# FPGA.net
KiCad netlist of a schematic drawn in Altium Designer
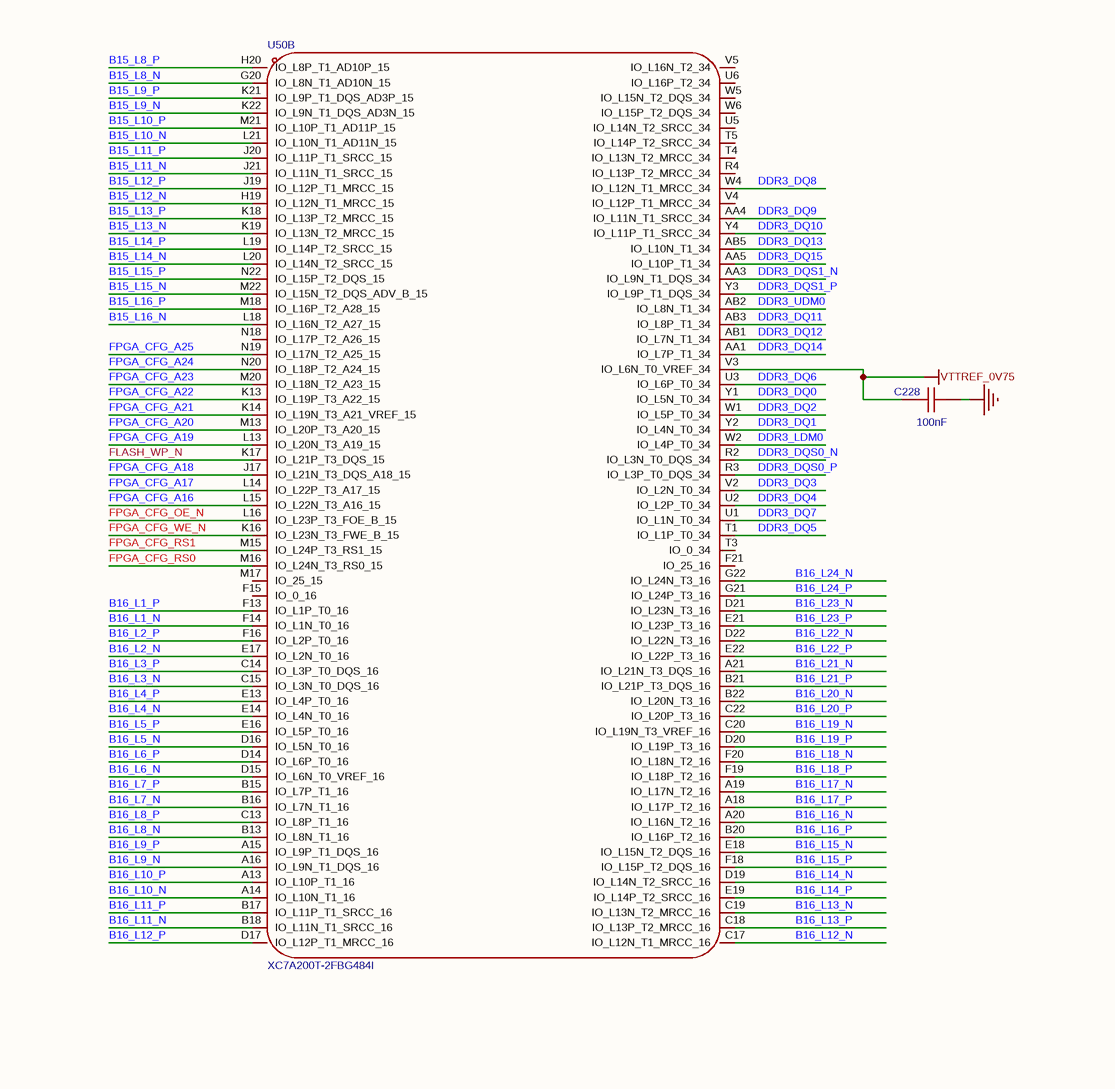
[diagram p0: FPGA.schdoc, top left]
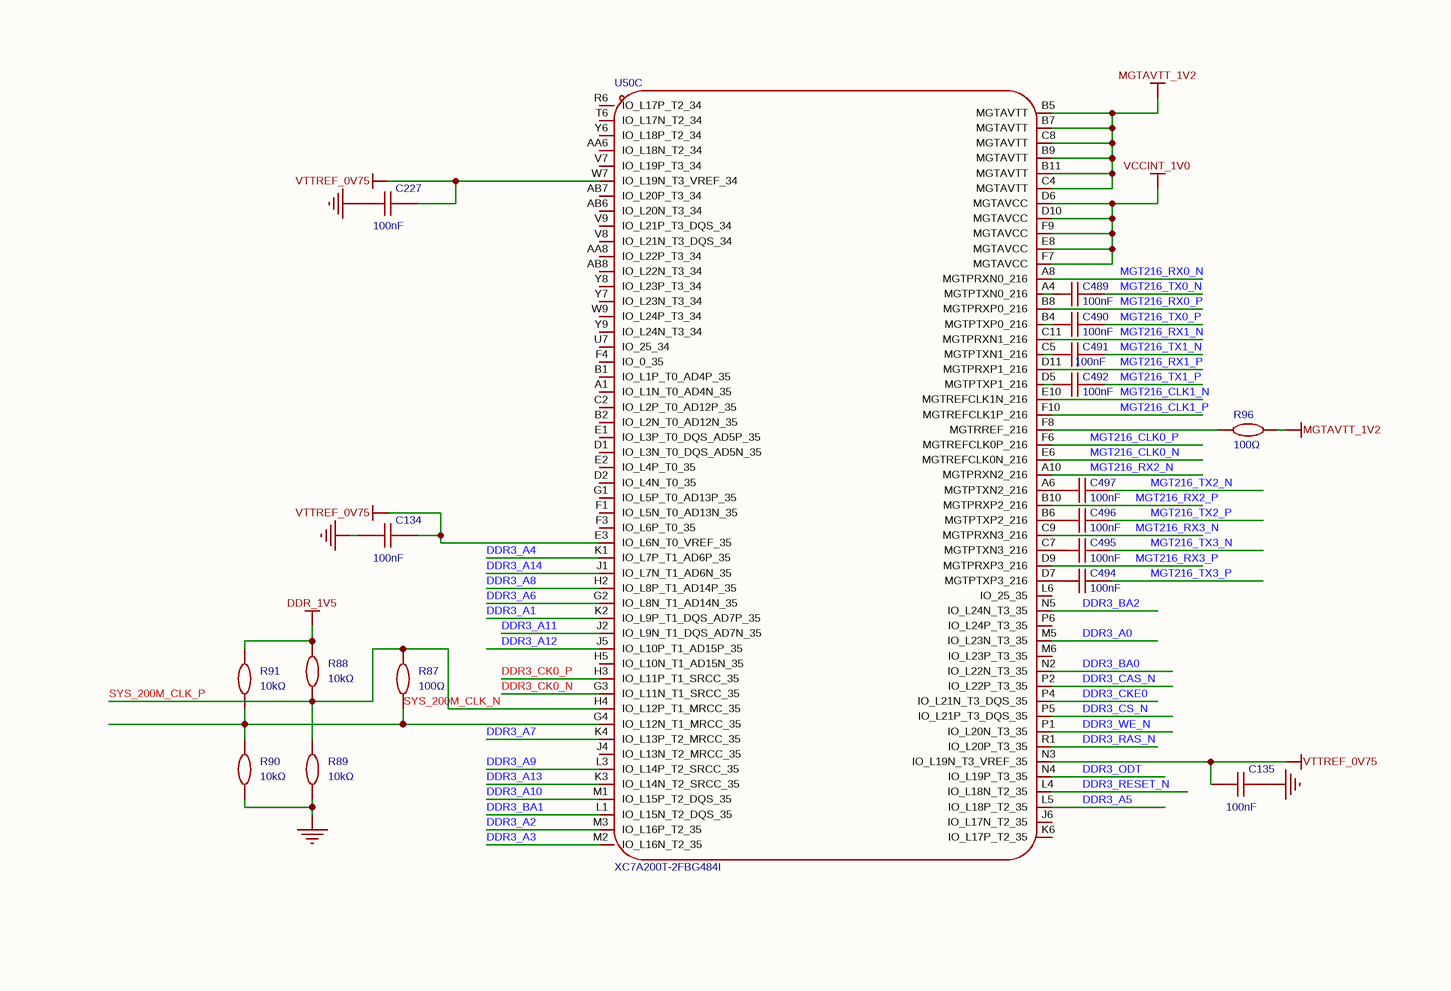
[diagram p1: FPGA.schdoc, top right]
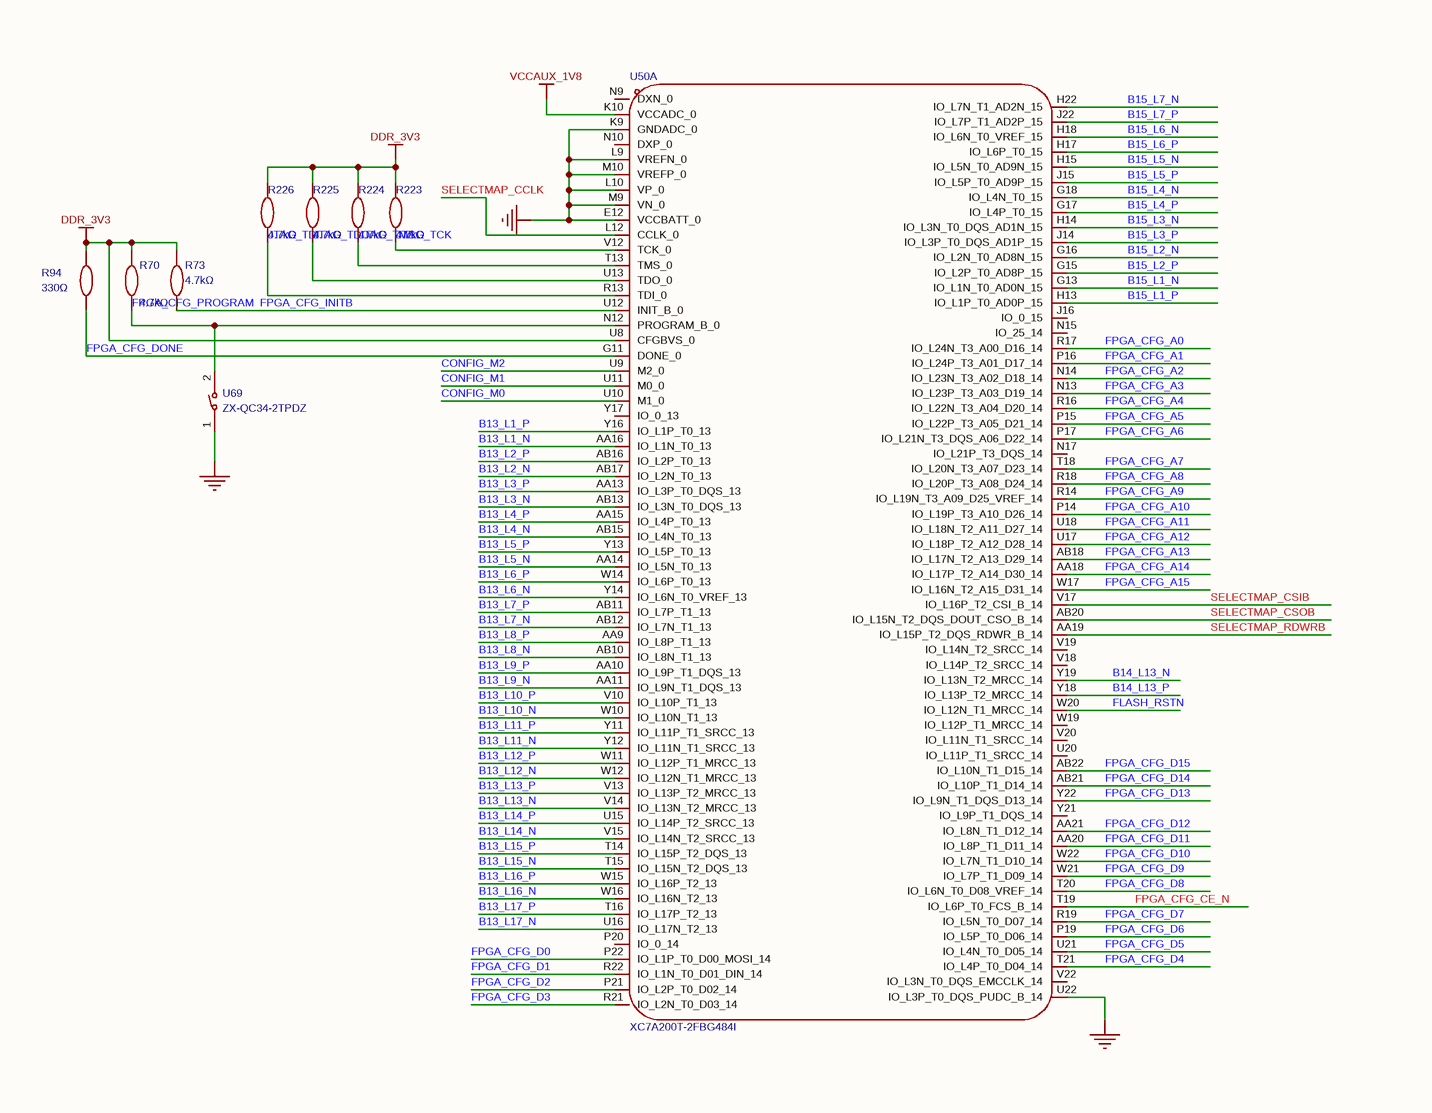
[diagram p2: FPGA.schdoc, bottom left]
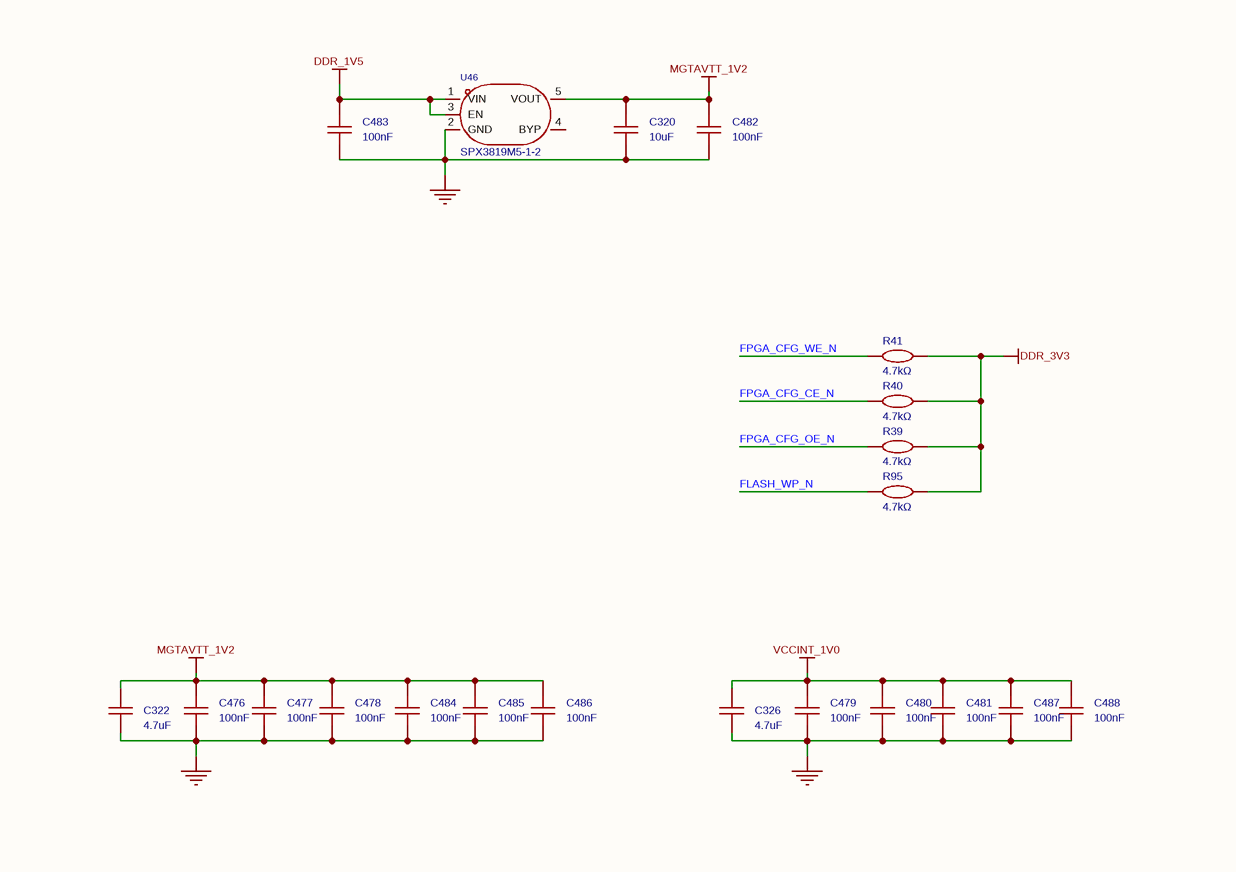
[diagram p3: FPGA.schdoc, bottom right]

(export (version "E")
  (design (tool "Eeschema 10.0.6"))
  (components
    (comp (ref "C134")
      (value "100nF")
      (footprint "C0402")
      (description "容值:100nF;精度:±10%;额定电压:50V;材质(温度系数):X7R;")
      (fields
        (field (name "MANUFACTURER") "muRata(村田)")
        (field (name "MANUFACTURER PART") "GRM155R71H104KE14D")
      )
      (libsource (lib "altium-import") (part "root_0_GRM155R71H104KE14D_"))
    )
    (comp (ref "C135")
      (value "100nF")
      (footprint "C0402")
      (description "容值:100nF;精度:±10%;额定电压:50V;材质(温度系数):X7R;")
      (fields
        (field (name "MANUFACTURER") "muRata(村田)")
        (field (name "MANUFACTURER PART") "GRM155R71H104KE14D")
      )
      (libsource (lib "altium-import") (part "root_0_GRM155R71H104KE14D_"))
    )
    (comp (ref "C227")
      (value "100nF")
      (footprint "C0402")
      (description "容值:100nF;精度:±10%;额定电压:50V;材质(温度系数):X7R;")
      (fields
        (field (name "MANUFACTURER") "muRata(村田)")
        (field (name "MANUFACTURER PART") "GRM155R71H104KE14D")
      )
      (libsource (lib "altium-import") (part "root_0_GRM155R71H104KE14D_"))
    )
    (comp (ref "C228")
      (value "100nF")
      (footprint "C0402")
      (description "容值:100nF;精度:±10%;额定电压:50V;材质(温度系数):X7R;")
      (fields
        (field (name "MANUFACTURER") "muRata(村田)")
        (field (name "MANUFACTURER PART") "GRM155R71H104KE14D")
      )
      (libsource (lib "altium-import") (part "root_0_mirrored_GRM155R71H104KE14D_"))
    )
    (comp (ref "C320")
      (value "10uF")
      (footprint "C0603")
      (description "容值:10uF;精度:±10%;额定电压:10V;材质(温度系数):X5R;")
      (fields
        (field (name "MANUFACTURER") "SAMSUNG(三星)")
        (field (name "MANUFACTURER PART") "CL10A106KP8NNNC")
      )
      (libsource (lib "altium-import") (part "root_1_CL10A106KP8NNNC_"))
    )
    (comp (ref "C322")
      (value "4.7uF")
      (footprint "C0603")
      (description "容值:4.7uF;精度:±10%;额定电压:16V;材质(温度系数):X5R;")
      (fields
        (field (name "MANUFACTURER PART") "CL10A475KO8NNNC")
        (field (name "MANUFACTURER") "SAMSUNG(三星)")
      )
      (libsource (lib "altium-import") (part "root_1_CL10A475KO8NNNC_"))
    )
    (comp (ref "C326")
      (value "4.7uF")
      (footprint "C0603")
      (description "容值:4.7uF;精度:±10%;额定电压:16V;材质(温度系数):X5R;")
      (fields
        (field (name "MANUFACTURER PART") "CL10A475KO8NNNC")
        (field (name "MANUFACTURER") "SAMSUNG(三星)")
      )
      (libsource (lib "altium-import") (part "root_1_CL10A475KO8NNNC_"))
    )
    (comp (ref "C476")
      (value "100nF")
      (footprint "C0402")
      (description "容值:100nF;精度:±10%;额定电压:50V;材质(温度系数):X7R;")
      (fields
        (field (name "MANUFACTURER") "muRata(村田)")
        (field (name "MANUFACTURER PART") "GRM155R71H104KE14D")
      )
      (libsource (lib "altium-import") (part "root_1_GRM155R71H104KE14D_"))
    )
    (comp (ref "C477")
      (value "100nF")
      (footprint "C0402")
      (description "容值:100nF;精度:±10%;额定电压:50V;材质(温度系数):X7R;")
      (fields
        (field (name "MANUFACTURER") "muRata(村田)")
        (field (name "MANUFACTURER PART") "GRM155R71H104KE14D")
      )
      (libsource (lib "altium-import") (part "root_1_GRM155R71H104KE14D_"))
    )
    (comp (ref "C478")
      (value "100nF")
      (footprint "C0402")
      (description "容值:100nF;精度:±10%;额定电压:50V;材质(温度系数):X7R;")
      (fields
        (field (name "MANUFACTURER") "muRata(村田)")
        (field (name "MANUFACTURER PART") "GRM155R71H104KE14D")
      )
      (libsource (lib "altium-import") (part "root_1_GRM155R71H104KE14D_"))
    )
    (comp (ref "C479")
      (value "100nF")
      (footprint "C0402")
      (description "容值:100nF;精度:±10%;额定电压:50V;材质(温度系数):X7R;")
      (fields
        (field (name "MANUFACTURER") "muRata(村田)")
        (field (name "MANUFACTURER PART") "GRM155R71H104KE14D")
      )
      (libsource (lib "altium-import") (part "root_1_GRM155R71H104KE14D_"))
    )
    (comp (ref "C480")
      (value "100nF")
      (footprint "C0402")
      (description "容值:100nF;精度:±10%;额定电压:50V;材质(温度系数):X7R;")
      (fields
        (field (name "MANUFACTURER") "muRata(村田)")
        (field (name "MANUFACTURER PART") "GRM155R71H104KE14D")
      )
      (libsource (lib "altium-import") (part "root_1_GRM155R71H104KE14D_"))
    )
    (comp (ref "C481")
      (value "100nF")
      (footprint "C0402")
      (description "容值:100nF;精度:±10%;额定电压:50V;材质(温度系数):X7R;")
      (fields
        (field (name "MANUFACTURER") "muRata(村田)")
        (field (name "MANUFACTURER PART") "GRM155R71H104KE14D")
      )
      (libsource (lib "altium-import") (part "root_1_GRM155R71H104KE14D_"))
    )
    (comp (ref "C482")
      (value "100nF")
      (footprint "C0402")
      (description "容值:100nF;精度:±10%;额定电压:50V;材质(温度系数):X7R;")
      (fields
        (field (name "MANUFACTURER") "muRata(村田)")
        (field (name "MANUFACTURER PART") "GRM155R71H104KE14D")
      )
      (libsource (lib "altium-import") (part "root_1_GRM155R71H104KE14D_"))
    )
    (comp (ref "C483")
      (value "100nF")
      (footprint "C0402")
      (description "容值:100nF;精度:±10%;额定电压:50V;材质(温度系数):X7R;")
      (fields
        (field (name "MANUFACTURER") "muRata(村田)")
        (field (name "MANUFACTURER PART") "GRM155R71H104KE14D")
      )
      (libsource (lib "altium-import") (part "root_1_GRM155R71H104KE14D_"))
    )
    (comp (ref "C484")
      (value "100nF")
      (footprint "C0402")
      (description "容值:100nF;精度:±10%;额定电压:50V;材质(温度系数):X7R;")
      (fields
        (field (name "MANUFACTURER") "muRata(村田)")
        (field (name "MANUFACTURER PART") "GRM155R71H104KE14D")
      )
      (libsource (lib "altium-import") (part "root_1_GRM155R71H104KE14D_"))
    )
    (comp (ref "C485")
      (value "100nF")
      (footprint "C0402")
      (description "容值:100nF;精度:±10%;额定电压:50V;材质(温度系数):X7R;")
      (fields
        (field (name "MANUFACTURER") "muRata(村田)")
        (field (name "MANUFACTURER PART") "GRM155R71H104KE14D")
      )
      (libsource (lib "altium-import") (part "root_1_GRM155R71H104KE14D_"))
    )
    (comp (ref "C486")
      (value "100nF")
      (footprint "C0402")
      (description "容值:100nF;精度:±10%;额定电压:50V;材质(温度系数):X7R;")
      (fields
        (field (name "MANUFACTURER") "muRata(村田)")
        (field (name "MANUFACTURER PART") "GRM155R71H104KE14D")
      )
      (libsource (lib "altium-import") (part "root_1_GRM155R71H104KE14D_"))
    )
    (comp (ref "C487")
      (value "100nF")
      (footprint "C0402")
      (description "容值:100nF;精度:±10%;额定电压:50V;材质(温度系数):X7R;")
      (fields
        (field (name "MANUFACTURER") "muRata(村田)")
        (field (name "MANUFACTURER PART") "GRM155R71H104KE14D")
      )
      (libsource (lib "altium-import") (part "root_1_GRM155R71H104KE14D_"))
    )
    (comp (ref "C488")
      (value "100nF")
      (footprint "C0402")
      (description "容值:100nF;精度:±10%;额定电压:50V;材质(温度系数):X7R;")
      (fields
        (field (name "MANUFACTURER") "muRata(村田)")
        (field (name "MANUFACTURER PART") "GRM155R71H104KE14D")
      )
      (libsource (lib "altium-import") (part "root_1_GRM155R71H104KE14D_"))
    )
    (comp (ref "C489")
      (value "100nF")
      (footprint "C0402")
      (description "容值:100nF;精度:±10%;额定电压:50V;材质(温度系数):X7R;")
      (fields
        (field (name "MANUFACTURER") "muRata(村田)")
        (field (name "MANUFACTURER PART") "GRM155R71H104KE14D")
      )
      (libsource (lib "altium-import") (part "root_2_GRM155R71H104KE14D_"))
    )
    (comp (ref "C490")
      (value "100nF")
      (footprint "C0402")
      (description "容值:100nF;精度:±10%;额定电压:50V;材质(温度系数):X7R;")
      (fields
        (field (name "MANUFACTURER") "muRata(村田)")
        (field (name "MANUFACTURER PART") "GRM155R71H104KE14D")
      )
      (libsource (lib "altium-import") (part "root_2_GRM155R71H104KE14D_"))
    )
    (comp (ref "C491")
      (value "100nF")
      (footprint "C0402")
      (description "容值:100nF;精度:±10%;额定电压:50V;材质(温度系数):X7R;")
      (fields
        (field (name "MANUFACTURER") "muRata(村田)")
        (field (name "MANUFACTURER PART") "GRM155R71H104KE14D")
      )
      (libsource (lib "altium-import") (part "root_2_GRM155R71H104KE14D_"))
    )
    (comp (ref "C492")
      (value "100nF")
      (footprint "C0402")
      (description "容值:100nF;精度:±10%;额定电压:50V;材质(温度系数):X7R;")
      (fields
        (field (name "MANUFACTURER") "muRata(村田)")
        (field (name "MANUFACTURER PART") "GRM155R71H104KE14D")
      )
      (libsource (lib "altium-import") (part "root_2_GRM155R71H104KE14D_"))
    )
    (comp (ref "C494")
      (value "100nF")
      (footprint "C0402")
      (description "容值:100nF;精度:±10%;额定电压:50V;材质(温度系数):X7R;")
      (fields
        (field (name "MANUFACTURER") "muRata(村田)")
        (field (name "MANUFACTURER PART") "GRM155R71H104KE14D")
      )
      (libsource (lib "altium-import") (part "root_2_GRM155R71H104KE14D_"))
    )
    (comp (ref "C495")
      (value "100nF")
      (footprint "C0402")
      (description "容值:100nF;精度:±10%;额定电压:50V;材质(温度系数):X7R;")
      (fields
        (field (name "MANUFACTURER") "muRata(村田)")
        (field (name "MANUFACTURER PART") "GRM155R71H104KE14D")
      )
      (libsource (lib "altium-import") (part "root_2_GRM155R71H104KE14D_"))
    )
    (comp (ref "C496")
      (value "100nF")
      (footprint "C0402")
      (description "容值:100nF;精度:±10%;额定电压:50V;材质(温度系数):X7R;")
      (fields
        (field (name "MANUFACTURER") "muRata(村田)")
        (field (name "MANUFACTURER PART") "GRM155R71H104KE14D")
      )
      (libsource (lib "altium-import") (part "root_2_GRM155R71H104KE14D_"))
    )
    (comp (ref "C497")
      (value "100nF")
      (footprint "C0402")
      (description "容值:100nF;精度:±10%;额定电压:50V;材质(温度系数):X7R;")
      (fields
        (field (name "MANUFACTURER") "muRata(村田)")
        (field (name "MANUFACTURER PART") "GRM155R71H104KE14D")
      )
      (libsource (lib "altium-import") (part "root_2_GRM155R71H104KE14D_"))
    )
    (comp (ref "R39")
      (value "4.7kΩ")
      (footprint "R0603")
      (description "电阻类型:厚膜电阻;阻值:4.7kΩ;精度:±1%;功率:100mW;最大工作电压:75V;温度系数:±100ppm/℃;")
      (fields
        (field (name "MANUFACTURER") "UNI-ROYAL(厚声)")
        (field (name "MANUFACTURER PART") "0603WAF4701T5E")
      )
      (libsource (lib "altium-import") (part "root_0_0603WAF4701T5E_"))
    )
    (comp (ref "R40")
      (value "4.7kΩ")
      (footprint "R0603")
      (description "电阻类型:厚膜电阻;阻值:4.7kΩ;精度:±1%;功率:100mW;最大工作电压:75V;温度系数:±100ppm/℃;")
      (fields
        (field (name "MANUFACTURER") "UNI-ROYAL(厚声)")
        (field (name "MANUFACTURER PART") "0603WAF4701T5E")
      )
      (libsource (lib "altium-import") (part "root_0_0603WAF4701T5E_"))
    )
    (comp (ref "R41")
      (value "4.7kΩ")
      (footprint "R0603")
      (description "电阻类型:厚膜电阻;阻值:4.7kΩ;精度:±1%;功率:100mW;最大工作电压:75V;温度系数:±100ppm/℃;")
      (fields
        (field (name "MANUFACTURER") "UNI-ROYAL(厚声)")
        (field (name "MANUFACTURER PART") "0603WAF4701T5E")
      )
      (libsource (lib "altium-import") (part "root_0_0603WAF4701T5E_"))
    )
    (comp (ref "R70")
      (value "4.7kΩ")
      (footprint "R0603")
      (description "电阻类型:厚膜电阻;阻值:4.7kΩ;精度:±1%;功率:100mW;最大工作电压:75V;温度系数:±100ppm/℃;")
      (fields
        (field (name "MANUFACTURER") "UNI-ROYAL(厚声)")
        (field (name "MANUFACTURER PART") "0603WAF4701T5E")
      )
      (libsource (lib "altium-import") (part "root_1_0603WAF4701T5E_"))
    )
    (comp (ref "R73")
      (value "4.7kΩ")
      (footprint "R0603")
      (description "电阻类型:厚膜电阻;阻值:4.7kΩ;精度:±1%;功率:100mW;最大工作电压:75V;温度系数:±100ppm/℃;")
      (fields
        (field (name "MANUFACTURER") "UNI-ROYAL(厚声)")
        (field (name "MANUFACTURER PART") "0603WAF4701T5E")
      )
      (libsource (lib "altium-import") (part "root_1_0603WAF4701T5E_"))
    )
    (comp (ref "R87")
      (value "100Ω")
      (footprint "R0603")
      (description "电阻类型:厚膜电阻;阻值:100Ω;精度:±1%;功率:100mW;最大工作电压:75V;温度系数:±200ppm/℃;")
      (fields
        (field (name "MANUFACTURER") "UNI-ROYAL(厚声)")
        (field (name "MANUFACTURERPART") "0603WAF1000T5E")
      )
      (libsource (lib "altium-import") (part "root_1_0603WAF1000T5E_"))
    )
    (comp (ref "R88")
      (value "10kΩ")
      (footprint "R0603")
      (description "电阻类型:厚膜电阻;阻值:10kΩ;精度:±1%;功率:100mW;最大工作电压:75V;温度系数:±100ppm/℃;")
      (fields
        (field (name "MANUFACTURER") "UNI-ROYAL(厚声)")
        (field (name "MANUFACTURER PART") "0603WAF1002T5E")
      )
      (libsource (lib "altium-import") (part "root_1_0603WAF1002T5E_"))
    )
    (comp (ref "R89")
      (value "10kΩ")
      (footprint "R0603")
      (description "电阻类型:厚膜电阻;阻值:10kΩ;精度:±1%;功率:100mW;最大工作电压:75V;温度系数:±100ppm/℃;")
      (fields
        (field (name "MANUFACTURER") "UNI-ROYAL(厚声)")
        (field (name "MANUFACTURER PART") "0603WAF1002T5E")
      )
      (libsource (lib "altium-import") (part "root_1_0603WAF1002T5E_"))
    )
    (comp (ref "R90")
      (value "10kΩ")
      (footprint "R0603")
      (description "电阻类型:厚膜电阻;阻值:10kΩ;精度:±1%;功率:100mW;最大工作电压:75V;温度系数:±100ppm/℃;")
      (fields
        (field (name "MANUFACTURER") "UNI-ROYAL(厚声)")
        (field (name "MANUFACTURER PART") "0603WAF1002T5E")
      )
      (libsource (lib "altium-import") (part "root_1_0603WAF1002T5E_"))
    )
    (comp (ref "R91")
      (value "10kΩ")
      (footprint "R0603")
      (description "电阻类型:厚膜电阻;阻值:10kΩ;精度:±1%;功率:100mW;最大工作电压:75V;温度系数:±100ppm/℃;")
      (fields
        (field (name "MANUFACTURER") "UNI-ROYAL(厚声)")
        (field (name "MANUFACTURER PART") "0603WAF1002T5E")
      )
      (libsource (lib "altium-import") (part "root_1_0603WAF1002T5E_"))
    )
    (comp (ref "R94")
      (value "330Ω")
      (footprint "R0603")
      (description "电阻类型:厚膜电阻;阻值:330Ω;精度:±1%;功率:100mW;最大工作电压:75V;温度系数:±100ppm/℃;")
      (fields
        (field (name "MANUFACTURER") "UNI-ROYAL(厚声)")
        (field (name "MANUFACTURER PART") "0603WAF3300T5E")
      )
      (libsource (lib "altium-import") (part "root_1_0603WAF3300T5E_"))
    )
    (comp (ref "R95")
      (value "4.7kΩ")
      (footprint "R0603")
      (description "电阻类型:厚膜电阻;阻值:4.7kΩ;精度:±1%;功率:100mW;最大工作电压:75V;温度系数:±100ppm/℃;")
      (fields
        (field (name "MANUFACTURER") "UNI-ROYAL(厚声)")
        (field (name "MANUFACTURER PART") "0603WAF4701T5E")
      )
      (libsource (lib "altium-import") (part "root_0_0603WAF4701T5E_"))
    )
    (comp (ref "R96")
      (value "100Ω")
      (footprint "R0402")
      (description "电阻类型:厚膜电阻;阻值:100Ω;精度:±1%;功率:62.5mW;最大工作电压:50V;温度系数:±200ppm/℃;")
      (fields
        (field (name "MANUFACTURER") "UNI-ROYAL(厚声)")
        (field (name "MANUFACTURERPART") "0402WGF1000TCE")
      )
      (libsource (lib "altium-import") (part "root_0_0402WGF1000TCE_"))
    )
    (comp (ref "R223")
      (value "4.7kΩ")
      (footprint "R0402")
      (description "电阻类型:厚膜电阻;阻值:4.7kΩ;精度:±1%;功率:62.5mW;最大工作电压:50V;温度系数:±100ppm/℃;")
      (fields
        (field (name "MANUFACTURER") "UNI-ROYAL(厚声)")
        (field (name "MANUFACTURER PART") "0402WGF4701TCE")
      )
      (libsource (lib "altium-import") (part "root_1_0402WGF4701TCE_"))
    )
    (comp (ref "R224")
      (value "4.7kΩ")
      (footprint "R0402")
      (description "电阻类型:厚膜电阻;阻值:4.7kΩ;精度:±1%;功率:62.5mW;最大工作电压:50V;温度系数:±100ppm/℃;")
      (fields
        (field (name "MANUFACTURER") "UNI-ROYAL(厚声)")
        (field (name "MANUFACTURER PART") "0402WGF4701TCE")
      )
      (libsource (lib "altium-import") (part "root_1_0402WGF4701TCE_"))
    )
    (comp (ref "R225")
      (value "4.7kΩ")
      (footprint "R0402")
      (description "电阻类型:厚膜电阻;阻值:4.7kΩ;精度:±1%;功率:62.5mW;最大工作电压:50V;温度系数:±100ppm/℃;")
      (fields
        (field (name "MANUFACTURER") "UNI-ROYAL(厚声)")
        (field (name "MANUFACTURER PART") "0402WGF4701TCE")
      )
      (libsource (lib "altium-import") (part "root_1_0402WGF4701TCE_"))
    )
    (comp (ref "R226")
      (value "4.7kΩ")
      (footprint "R0402")
      (description "电阻类型:厚膜电阻;阻值:4.7kΩ;精度:±1%;功率:62.5mW;最大工作电压:50V;温度系数:±100ppm/℃;")
      (fields
        (field (name "MANUFACTURER") "UNI-ROYAL(厚声)")
        (field (name "MANUFACTURER PART") "0402WGF4701TCE")
      )
      (libsource (lib "altium-import") (part "root_1_0402WGF4701TCE_"))
    )
    (comp (ref "U46")
      (value "SPX3819M5-1-2")
      (footprint "SOT-23-5_L2.9-W1.6-P0.95-LS2.8-BR")
      (fields (field (name "MANUFACTURER") "SIPEX"))
      (libsource (lib "altium-import") (part "root_0_SPX3819M5-1-2_"))
    )
    (comp (ref "U50")
      (value "XC7A200T-2FBG484I")
      (footprint "FBGA-484_L23.0-W23.0-R22-C22-P1.00-TL")
      (fields (field (name "MANUFACTURER") "AMD/XILINX(赛灵思)"))
      (libsource (lib "altium-import") (part "root_0_XC7A200T-2FBG484I_"))
    )
    (comp (ref "U69")
      (value "ZX-QC34-2TPDZ")
      (footprint "KEY-SMD_L3.9-W3.0-LS5.0-EH")
      (fields (field (name "MANUFACTURER") "Megastar(兆星)"))
      (libsource (lib "altium-import") (part "root_1_ZX-QC34-2TPDZ_"))
    )
  )
  (nets
    (net (code "1") (name "/B13_L1_N") (class "Default")
      (node (ref "U50") (pin "AA16") (pinfunction "IO_L1N_T0_13_AA16") (pintype "passive"))
    )
    (net (code "2") (name "/B13_L1_P") (class "Default")
      (node (ref "U50") (pin "Y16") (pinfunction "IO_L1P_T0_13_Y16") (pintype "passive"))
    )
    (net (code "3") (name "/B13_L2_N") (class "Default")
      (node (ref "U50") (pin "AB17") (pinfunction "IO_L2N_T0_13_AB17") (pintype "passive"))
    )
    (net (code "4") (name "/B13_L2_P") (class "Default")
      (node (ref "U50") (pin "AB16") (pinfunction "IO_L2P_T0_13_AB16") (pintype "passive"))
    )
    (net (code "5") (name "/B13_L3_N") (class "Default")
      (node (ref "U50") (pin "AB13") (pinfunction "IO_L3N_T0_DQS_13_AB13") (pintype "passive"))
    )
    (net (code "6") (name "/B13_L3_P") (class "Default")
      (node (ref "U50") (pin "AA13") (pinfunction "IO_L3P_T0_DQS_13_AA13") (pintype "passive"))
    )
    (net (code "7") (name "/B13_L4_N") (class "Default")
      (node (ref "U50") (pin "AB15") (pinfunction "IO_L4N_T0_13_AB15") (pintype "passive"))
    )
    (net (code "8") (name "/B13_L4_P") (class "Default")
      (node (ref "U50") (pin "AA15") (pinfunction "IO_L4P_T0_13_AA15") (pintype "passive"))
    )
    (net (code "9") (name "/B13_L5_N") (class "Default")
      (node (ref "U50") (pin "AA14") (pinfunction "IO_L5N_T0_13_AA14") (pintype "passive"))
    )
    (net (code "10") (name "/B13_L5_P") (class "Default")
      (node (ref "U50") (pin "Y13") (pinfunction "IO_L5P_T0_13_Y13") (pintype "passive"))
    )
    (net (code "11") (name "/B13_L6_N") (class "Default")
      (node (ref "U50") (pin "Y14") (pinfunction "IO_L6N_T0_VREF_13_Y14") (pintype "passive"))
    )
    (net (code "12") (name "/B13_L6_P") (class "Default")
      (node (ref "U50") (pin "W14") (pinfunction "IO_L6P_T0_13_W14") (pintype "passive"))
    )
    (net (code "13") (name "/B13_L7_N") (class "Default")
      (node (ref "U50") (pin "AB12") (pinfunction "IO_L7N_T1_13_AB12") (pintype "passive"))
    )
    (net (code "14") (name "/B13_L7_P") (class "Default")
      (node (ref "U50") (pin "AB11") (pinfunction "IO_L7P_T1_13_AB11") (pintype "passive"))
    )
    (net (code "15") (name "/B13_L8_N") (class "Default")
      (node (ref "U50") (pin "AB10") (pinfunction "IO_L8N_T1_13_AB10") (pintype "passive"))
    )
    (net (code "16") (name "/B13_L8_P") (class "Default")
      (node (ref "U50") (pin "AA9") (pinfunction "IO_L8P_T1_13_AA9") (pintype "passive"))
    )
    (net (code "17") (name "/B13_L9_N") (class "Default")
      (node (ref "U50") (pin "AA11") (pinfunction "IO_L9N_T1_DQS_13_AA11") (pintype "passive"))
    )
    (net (code "18") (name "/B13_L9_P") (class "Default")
      (node (ref "U50") (pin "AA10") (pinfunction "IO_L9P_T1_DQS_13_AA10") (pintype "passive"))
    )
    (net (code "19") (name "/B13_L10_N") (class "Default")
      (node (ref "U50") (pin "W10") (pinfunction "IO_L10N_T1_13_W10") (pintype "passive"))
    )
    (net (code "20") (name "/B13_L10_P") (class "Default")
      (node (ref "U50") (pin "V10") (pinfunction "IO_L10P_T1_13_V10") (pintype "passive"))
    )
    (net (code "21") (name "/B13_L11_N") (class "Default")
      (node (ref "U50") (pin "Y12") (pinfunction "IO_L11N_T1_SRCC_13_Y12") (pintype "passive"))
    )
    (net (code "22") (name "/B13_L11_P") (class "Default")
      (node (ref "U50") (pin "Y11") (pinfunction "IO_L11P_T1_SRCC_13_Y11") (pintype "passive"))
    )
    (net (code "23") (name "/B13_L12_N") (class "Default")
      (node (ref "U50") (pin "W12") (pinfunction "IO_L12N_T1_MRCC_13_W12") (pintype "passive"))
    )
    (net (code "24") (name "/B13_L12_P") (class "Default")
      (node (ref "U50") (pin "W11") (pinfunction "IO_L12P_T1_MRCC_13_W11") (pintype "passive"))
    )
    (net (code "25") (name "/B13_L13_N") (class "Default")
      (node (ref "U50") (pin "V14") (pinfunction "IO_L13N_T2_MRCC_13_V14") (pintype "passive"))
    )
    (net (code "26") (name "/B13_L13_P") (class "Default")
      (node (ref "U50") (pin "V13") (pinfunction "IO_L13P_T2_MRCC_13_V13") (pintype "passive"))
    )
    (net (code "27") (name "/B13_L14_N") (class "Default")
      (node (ref "U50") (pin "V15") (pinfunction "IO_L14N_T2_SRCC_13_V15") (pintype "passive"))
    )
    (net (code "28") (name "/B13_L14_P") (class "Default")
      (node (ref "U50") (pin "U15") (pinfunction "IO_L14P_T2_SRCC_13_U15") (pintype "passive"))
    )
    (net (code "29") (name "/B13_L15_N") (class "Default")
      (node (ref "U50") (pin "T15") (pinfunction "IO_L15N_T2_DQS_13_T15") (pintype "passive"))
    )
    (net (code "30") (name "/B13_L15_P") (class "Default")
      (node (ref "U50") (pin "T14") (pinfunction "IO_L15P_T2_DQS_13_T14") (pintype "passive"))
    )
    (net (code "31") (name "/B13_L16_N") (class "Default")
      (node (ref "U50") (pin "W16") (pinfunction "IO_L16N_T2_13_W16") (pintype "passive"))
    )
    (net (code "32") (name "/B13_L16_P") (class "Default")
      (node (ref "U50") (pin "W15") (pinfunction "IO_L16P_T2_13_W15") (pintype "passive"))
    )
    (net (code "33") (name "/B13_L17_N") (class "Default")
      (node (ref "U50") (pin "U16") (pinfunction "IO_L17N_T2_13_U16") (pintype "passive"))
    )
    (net (code "34") (name "/B13_L17_P") (class "Default")
      (node (ref "U50") (pin "T16") (pinfunction "IO_L17P_T2_13_T16") (pintype "passive"))
    )
    (net (code "35") (name "/B14_L13_N") (class "Default")
      (node (ref "U50") (pin "Y19") (pinfunction "IO_L13N_T2_MRCC_14_Y19") (pintype "passive"))
    )
    (net (code "36") (name "/B14_L13_P") (class "Default")
      (node (ref "U50") (pin "Y18") (pinfunction "IO_L13P_T2_MRCC_14_Y18") (pintype "passive"))
    )
    (net (code "37") (name "/B15_L1_N") (class "Default")
      (node (ref "U50") (pin "G13") (pinfunction "IO_L1N_T0_AD0N_15_G13") (pintype "passive"))
    )
    (net (code "38") (name "/B15_L1_P") (class "Default")
      (node (ref "U50") (pin "H13") (pinfunction "IO_L1P_T0_AD0P_15_H13") (pintype "passive"))
    )
    (net (code "39") (name "/B15_L2_N") (class "Default")
      (node (ref "U50") (pin "G16") (pinfunction "IO_L2N_T0_AD8N_15_G16") (pintype "passive"))
    )
    (net (code "40") (name "/B15_L2_P") (class "Default")
      (node (ref "U50") (pin "G15") (pinfunction "IO_L2P_T0_AD8P_15_G15") (pintype "passive"))
    )
    (net (code "41") (name "/B15_L3_N") (class "Default")
      (node (ref "U50") (pin "H14") (pinfunction "IO_L3N_T0_DQS_AD1N_15_H14") (pintype "passive"))
    )
    (net (code "42") (name "/B15_L3_P") (class "Default")
      (node (ref "U50") (pin "J14") (pinfunction "IO_L3P_T0_DQS_AD1P_15_J14") (pintype "passive"))
    )
    (net (code "43") (name "/B15_L4_N") (class "Default")
      (node (ref "U50") (pin "G18") (pinfunction "IO_L4N_T0_15_G18") (pintype "passive"))
    )
    (net (code "44") (name "/B15_L4_P") (class "Default")
      (node (ref "U50") (pin "G17") (pinfunction "IO_L4P_T0_15_G17") (pintype "passive"))
    )
    (net (code "45") (name "/B15_L5_N") (class "Default")
      (node (ref "U50") (pin "H15") (pinfunction "IO_L5N_T0_AD9N_15_H15") (pintype "passive"))
    )
    (net (code "46") (name "/B15_L5_P") (class "Default")
      (node (ref "U50") (pin "J15") (pinfunction "IO_L5P_T0_AD9P_15_J15") (pintype "passive"))
    )
    (net (code "47") (name "/B15_L6_N") (class "Default")
      (node (ref "U50") (pin "H18") (pinfunction "IO_L6N_T0_VREF_15_H18") (pintype "passive"))
    )
    (net (code "48") (name "/B15_L6_P") (class "Default")
      (node (ref "U50") (pin "H17") (pinfunction "IO_L6P_T0_15_H17") (pintype "passive"))
    )
    (net (code "49") (name "/B15_L7_N") (class "Default")
      (node (ref "U50") (pin "H22") (pinfunction "IO_L7N_T1_AD2N_15_H22") (pintype "passive"))
    )
    (net (code "50") (name "/B15_L7_P") (class "Default")
      (node (ref "U50") (pin "J22") (pinfunction "IO_L7P_T1_AD2P_15_J22") (pintype "passive"))
    )
    (net (code "51") (name "/B15_L8_N") (class "Default")
      (node (ref "U50") (pin "G20") (pinfunction "IO_L8N_T1_AD10N_15_G20") (pintype "passive"))
    )
    (net (code "52") (name "/B15_L8_P") (class "Default")
      (node (ref "U50") (pin "H20") (pinfunction "IO_L8P_T1_AD10P_15_H20") (pintype "passive"))
    )
    (net (code "53") (name "/B15_L9_N") (class "Default")
      (node (ref "U50") (pin "K22") (pinfunction "IO_L9N_T1_DQS_AD3N_15_K22") (pintype "passive"))
    )
    (net (code "54") (name "/B15_L9_P") (class "Default")
      (node (ref "U50") (pin "K21") (pinfunction "IO_L9P_T1_DQS_AD3P_15_K21") (pintype "passive"))
    )
    (net (code "55") (name "/B15_L10_N") (class "Default")
      (node (ref "U50") (pin "L21") (pinfunction "IO_L10N_T1_AD11N_15_L21") (pintype "passive"))
    )
    (net (code "56") (name "/B15_L10_P") (class "Default")
      (node (ref "U50") (pin "M21") (pinfunction "IO_L10P_T1_AD11P_15_M21") (pintype "passive"))
    )
    (net (code "57") (name "/B15_L11_N") (class "Default")
      (node (ref "U50") (pin "J21") (pinfunction "IO_L11N_T1_SRCC_15_J21") (pintype "passive"))
    )
    (net (code "58") (name "/B15_L11_P") (class "Default")
      (node (ref "U50") (pin "J20") (pinfunction "IO_L11P_T1_SRCC_15_J20") (pintype "passive"))
    )
    (net (code "59") (name "/B15_L12_N") (class "Default")
      (node (ref "U50") (pin "H19") (pinfunction "IO_L12N_T1_MRCC_15_H19") (pintype "passive"))
    )
    (net (code "60") (name "/B15_L12_P") (class "Default")
      (node (ref "U50") (pin "J19") (pinfunction "IO_L12P_T1_MRCC_15_J19") (pintype "passive"))
    )
    (net (code "61") (name "/B15_L13_N") (class "Default")
      (node (ref "U50") (pin "K19") (pinfunction "IO_L13N_T2_MRCC_15_K19") (pintype "passive"))
    )
    (net (code "62") (name "/B15_L13_P") (class "Default")
      (node (ref "U50") (pin "K18") (pinfunction "IO_L13P_T2_MRCC_15_K18") (pintype "passive"))
    )
    (net (code "63") (name "/B15_L14_N") (class "Default")
      (node (ref "U50") (pin "L20") (pinfunction "IO_L14N_T2_SRCC_15_L20") (pintype "passive"))
    )
    (net (code "64") (name "/B15_L14_P") (class "Default")
      (node (ref "U50") (pin "L19") (pinfunction "IO_L14P_T2_SRCC_15_L19") (pintype "passive"))
    )
    (net (code "65") (name "/B15_L15_N") (class "Default")
      (node (ref "U50") (pin "M22") (pinfunction "IO_L15N_T2_DQS_ADV_B_15_M22") (pintype "passive"))
    )
    (net (code "66") (name "/B15_L15_P") (class "Default")
      (node (ref "U50") (pin "N22") (pinfunction "IO_L15P_T2_DQS_15_N22") (pintype "passive"))
    )
    (net (code "67") (name "/B15_L16_N") (class "Default")
      (node (ref "U50") (pin "L18") (pinfunction "IO_L16N_T2_A27_15_L18") (pintype "passive"))
    )
    (net (code "68") (name "/B15_L16_P") (class "Default")
      (node (ref "U50") (pin "M18") (pinfunction "IO_L16P_T2_A28_15_M18") (pintype "passive"))
    )
    (net (code "69") (name "/B16_L1_N") (class "Default")
      (node (ref "U50") (pin "F14") (pinfunction "IO_L1N_T0_16_F14") (pintype "passive"))
    )
    (net (code "70") (name "/B16_L1_P") (class "Default")
      (node (ref "U50") (pin "F13") (pinfunction "IO_L1P_T0_16_F13") (pintype "passive"))
    )
    (net (code "71") (name "/B16_L2_N") (class "Default")
      (node (ref "U50") (pin "E17") (pinfunction "IO_L2N_T0_16_E17") (pintype "passive"))
    )
    (net (code "72") (name "/B16_L2_P") (class "Default")
      (node (ref "U50") (pin "F16") (pinfunction "IO_L2P_T0_16_F16") (pintype "passive"))
    )
    (net (code "73") (name "/B16_L3_N") (class "Default")
      (node (ref "U50") (pin "C15") (pinfunction "IO_L3N_T0_DQS_16_C15") (pintype "passive"))
    )
    (net (code "74") (name "/B16_L3_P") (class "Default")
      (node (ref "U50") (pin "C14") (pinfunction "IO_L3P_T0_DQS_16_C14") (pintype "passive"))
    )
    (net (code "75") (name "/B16_L4_N") (class "Default")
      (node (ref "U50") (pin "E14") (pinfunction "IO_L4N_T0_16_E14") (pintype "passive"))
    )
    (net (code "76") (name "/B16_L4_P") (class "Default")
      (node (ref "U50") (pin "E13") (pinfunction "IO_L4P_T0_16_E13") (pintype "passive"))
    )
    (net (code "77") (name "/B16_L5_N") (class "Default")
      (node (ref "U50") (pin "D16") (pinfunction "IO_L5N_T0_16_D16") (pintype "passive"))
    )
    (net (code "78") (name "/B16_L5_P") (class "Default")
      (node (ref "U50") (pin "E16") (pinfunction "IO_L5P_T0_16_E16") (pintype "passive"))
    )
    (net (code "79") (name "/B16_L6_N") (class "Default")
      (node (ref "U50") (pin "D15") (pinfunction "IO_L6N_T0_VREF_16_D15") (pintype "passive"))
    )
    (net (code "80") (name "/B16_L6_P") (class "Default")
      (node (ref "U50") (pin "D14") (pinfunction "IO_L6P_T0_16_D14") (pintype "passive"))
    )
    (net (code "81") (name "/B16_L7_N") (class "Default")
      (node (ref "U50") (pin "B16") (pinfunction "IO_L7N_T1_16_B16") (pintype "passive"))
    )
    (net (code "82") (name "/B16_L7_P") (class "Default")
      (node (ref "U50") (pin "B15") (pinfunction "IO_L7P_T1_16_B15") (pintype "passive"))
    )
    (net (code "83") (name "/B16_L8_N") (class "Default")
      (node (ref "U50") (pin "B13") (pinfunction "IO_L8N_T1_16_B13") (pintype "passive"))
    )
    (net (code "84") (name "/B16_L8_P") (class "Default")
      (node (ref "U50") (pin "C13") (pinfunction "IO_L8P_T1_16_C13") (pintype "passive"))
    )
    (net (code "85") (name "/B16_L9_N") (class "Default")
      (node (ref "U50") (pin "A16") (pinfunction "IO_L9N_T1_DQS_16_A16") (pintype "passive"))
    )
    (net (code "86") (name "/B16_L9_P") (class "Default")
      (node (ref "U50") (pin "A15") (pinfunction "IO_L9P_T1_DQS_16_A15") (pintype "passive"))
    )
    (net (code "87") (name "/B16_L10_N") (class "Default")
      (node (ref "U50") (pin "A14") (pinfunction "IO_L10N_T1_16_A14") (pintype "passive"))
    )
    (net (code "88") (name "/B16_L10_P") (class "Default")
      (node (ref "U50") (pin "A13") (pinfunction "IO_L10P_T1_16_A13") (pintype "passive"))
    )
    (net (code "89") (name "/B16_L11_N") (class "Default")
      (node (ref "U50") (pin "B18") (pinfunction "IO_L11N_T1_SRCC_16_B18") (pintype "passive"))
    )
    (net (code "90") (name "/B16_L11_P") (class "Default")
      (node (ref "U50") (pin "B17") (pinfunction "IO_L11P_T1_SRCC_16_B17") (pintype "passive"))
    )
    (net (code "91") (name "/B16_L12_N") (class "Default")
      (node (ref "U50") (pin "C17") (pinfunction "IO_L12N_T1_MRCC_16_C17") (pintype "passive"))
    )
    (net (code "92") (name "/B16_L12_P") (class "Default")
      (node (ref "U50") (pin "D17") (pinfunction "IO_L12P_T1_MRCC_16_D17") (pintype "passive"))
    )
    (net (code "93") (name "/B16_L13_N") (class "Default")
      (node (ref "U50") (pin "C19") (pinfunction "IO_L13N_T2_MRCC_16_C19") (pintype "passive"))
    )
    (net (code "94") (name "/B16_L13_P") (class "Default")
      (node (ref "U50") (pin "C18") (pinfunction "IO_L13P_T2_MRCC_16_C18") (pintype "passive"))
    )
    (net (code "95") (name "/B16_L14_N") (class "Default")
      (node (ref "U50") (pin "D19") (pinfunction "IO_L14N_T2_SRCC_16_D19") (pintype "passive"))
    )
    (net (code "96") (name "/B16_L14_P") (class "Default")
      (node (ref "U50") (pin "E19") (pinfunction "IO_L14P_T2_SRCC_16_E19") (pintype "passive"))
    )
    (net (code "97") (name "/B16_L15_N") (class "Default")
      (node (ref "U50") (pin "E18") (pinfunction "IO_L15N_T2_DQS_16_E18") (pintype "passive"))
    )
    (net (code "98") (name "/B16_L15_P") (class "Default")
      (node (ref "U50") (pin "F18") (pinfunction "IO_L15P_T2_DQS_16_F18") (pintype "passive"))
    )
    (net (code "99") (name "/B16_L16_N") (class "Default")
      (node (ref "U50") (pin "A20") (pinfunction "IO_L16N_T2_16_A20") (pintype "passive"))
    )
    (net (code "100") (name "/B16_L16_P") (class "Default")
      (node (ref "U50") (pin "B20") (pinfunction "IO_L16P_T2_16_B20") (pintype "passive"))
    )
    (net (code "101") (name "/B16_L17_N") (class "Default")
      (node (ref "U50") (pin "A19") (pinfunction "IO_L17N_T2_16_A19") (pintype "passive"))
    )
    (net (code "102") (name "/B16_L17_P") (class "Default")
      (node (ref "U50") (pin "A18") (pinfunction "IO_L17P_T2_16_A18") (pintype "passive"))
    )
    (net (code "103") (name "/B16_L18_N") (class "Default")
      (node (ref "U50") (pin "F20") (pinfunction "IO_L18N_T2_16_F20") (pintype "passive"))
    )
    (net (code "104") (name "/B16_L18_P") (class "Default")
      (node (ref "U50") (pin "F19") (pinfunction "IO_L18P_T2_16_F19") (pintype "passive"))
    )
    (net (code "105") (name "/B16_L19_N") (class "Default")
      (node (ref "U50") (pin "C20") (pinfunction "IO_L19N_T3_VREF_16_C20") (pintype "passive"))
    )
    (net (code "106") (name "/B16_L19_P") (class "Default")
      (node (ref "U50") (pin "D20") (pinfunction "IO_L19P_T3_16_D20") (pintype "passive"))
    )
    (net (code "107") (name "/B16_L20_N") (class "Default")
      (node (ref "U50") (pin "B22") (pinfunction "IO_L20N_T3_16_B22") (pintype "passive"))
    )
    (net (code "108") (name "/B16_L20_P") (class "Default")
      (node (ref "U50") (pin "C22") (pinfunction "IO_L20P_T3_16_C22") (pintype "passive"))
    )
    (net (code "109") (name "/B16_L21_N") (class "Default")
      (node (ref "U50") (pin "A21") (pinfunction "IO_L21N_T3_DQS_16_A21") (pintype "passive"))
    )
    (net (code "110") (name "/B16_L21_P") (class "Default")
      (node (ref "U50") (pin "B21") (pinfunction "IO_L21P_T3_DQS_16_B21") (pintype "passive"))
    )
    (net (code "111") (name "/B16_L22_N") (class "Default")
      (node (ref "U50") (pin "D22") (pinfunction "IO_L22N_T3_16_D22") (pintype "passive"))
    )
    (net (code "112") (name "/B16_L22_P") (class "Default")
      (node (ref "U50") (pin "E22") (pinfunction "IO_L22P_T3_16_E22") (pintype "passive"))
    )
    (net (code "113") (name "/B16_L23_N") (class "Default")
      (node (ref "U50") (pin "D21") (pinfunction "IO_L23N_T3_16_D21") (pintype "passive"))
    )
    (net (code "114") (name "/B16_L23_P") (class "Default")
      (node (ref "U50") (pin "E21") (pinfunction "IO_L23P_T3_16_E21") (pintype "passive"))
    )
    (net (code "115") (name "/B16_L24_N") (class "Default")
      (node (ref "U50") (pin "G22") (pinfunction "IO_L24N_T3_16_G22") (pintype "passive"))
    )
    (net (code "116") (name "/B16_L24_P") (class "Default")
      (node (ref "U50") (pin "G21") (pinfunction "IO_L24P_T3_16_G21") (pintype "passive"))
    )
    (net (code "117") (name "/CONFIG_M0") (class "Default")
      (node (ref "U50") (pin "U10") (pinfunction "M1_0_U10") (pintype "passive"))
    )
    (net (code "118") (name "/CONFIG_M1") (class "Default")
      (node (ref "U50") (pin "U11") (pinfunction "M0_0_U11") (pintype "passive"))
    )
    (net (code "119") (name "/CONFIG_M2") (class "Default")
      (node (ref "U50") (pin "U9") (pinfunction "M2_0_U9") (pintype "passive"))
    )
    (net (code "120") (name "/DDR3_A0") (class "Default")
      (node (ref "U50") (pin "M5") (pinfunction "IO_L23N_T3_35_M5") (pintype "passive"))
    )
    (net (code "121") (name "/DDR3_A1") (class "Default")
      (node (ref "U50") (pin "K2") (pinfunction "IO_L9P_T1_DQS_AD7P_35_K2") (pintype "passive"))
    )
    (net (code "122") (name "/DDR3_A2") (class "Default")
      (node (ref "U50") (pin "M3") (pinfunction "IO_L16P_T2_35_M3") (pintype "passive"))
    )
    (net (code "123") (name "/DDR3_A3") (class "Default")
      (node (ref "U50") (pin "M2") (pinfunction "IO_L16N_T2_35_M2") (pintype "passive"))
    )
    (net (code "124") (name "/DDR3_A4") (class "Default")
      (node (ref "U50") (pin "K1") (pinfunction "IO_L7P_T1_AD6P_35_K1") (pintype "passive"))
    )
    (net (code "125") (name "/DDR3_A5") (class "Default")
      (node (ref "U50") (pin "L5") (pinfunction "IO_L18P_T2_35_L5") (pintype "passive"))
    )
    (net (code "126") (name "/DDR3_A6") (class "Default")
      (node (ref "U50") (pin "G2") (pinfunction "IO_L8N_T1_AD14N_35_G2") (pintype "passive"))
    )
    (net (code "127") (name "/DDR3_A7") (class "Default")
      (node (ref "U50") (pin "K4") (pinfunction "IO_L13P_T2_MRCC_35_K4") (pintype "passive"))
    )
    (net (code "128") (name "/DDR3_A8") (class "Default")
      (node (ref "U50") (pin "H2") (pinfunction "IO_L8P_T1_AD14P_35_H2") (pintype "passive"))
    )
    (net (code "129") (name "/DDR3_A9") (class "Default")
      (node (ref "U50") (pin "L3") (pinfunction "IO_L14P_T2_SRCC_35_L3") (pintype "passive"))
    )
    (net (code "130") (name "/DDR3_A10") (class "Default")
      (node (ref "U50") (pin "M1") (pinfunction "IO_L15P_T2_DQS_35_M1") (pintype "passive"))
    )
    (net (code "131") (name "/DDR3_A11") (class "Default")
      (node (ref "U50") (pin "J2") (pinfunction "IO_L9N_T1_DQS_AD7N_35_J2") (pintype "passive"))
    )
    (net (code "132") (name "/DDR3_A12") (class "Default")
      (node (ref "U50") (pin "J5") (pinfunction "IO_L10P_T1_AD15P_35_J5") (pintype "passive"))
    )
    (net (code "133") (name "/DDR3_A13") (class "Default")
      (node (ref "U50") (pin "K3") (pinfunction "IO_L14N_T2_SRCC_35_K3") (pintype "passive"))
    )
    (net (code "134") (name "/DDR3_A14") (class "Default")
      (node (ref "U50") (pin "J1") (pinfunction "IO_L7N_T1_AD6N_35_J1") (pintype "passive"))
    )
    (net (code "135") (name "/DDR3_BA0") (class "Default")
      (node (ref "U50") (pin "N2") (pinfunction "IO_L22N_T3_35_N2") (pintype "passive"))
    )
    (net (code "136") (name "/DDR3_BA1") (class "Default")
      (node (ref "U50") (pin "L1") (pinfunction "IO_L15N_T2_DQS_35_L1") (pintype "passive"))
    )
    (net (code "137") (name "/DDR3_BA2") (class "Default")
      (node (ref "U50") (pin "N5") (pinfunction "IO_L24N_T3_35_N5") (pintype "passive"))
    )
    (net (code "138") (name "/DDR3_CAS_N") (class "Default")
      (node (ref "U50") (pin "P2") (pinfunction "IO_L22P_T3_35_P2") (pintype "passive"))
    )
    (net (code "139") (name "/DDR3_CK0_N") (class "Default")
      (node (ref "U50") (pin "G3") (pinfunction "IO_L11N_T1_SRCC_35_G3") (pintype "passive"))
    )
    (net (code "140") (name "/DDR3_CK0_P") (class "Default")
      (node (ref "U50") (pin "H3") (pinfunction "IO_L11P_T1_SRCC_35_H3") (pintype "passive"))
    )
    (net (code "141") (name "/DDR3_CKE0") (class "Default")
      (node (ref "U50") (pin "P4") (pinfunction "IO_L21N_T3_DQS_35_P4") (pintype "passive"))
    )
    (net (code "142") (name "/DDR3_CS_N") (class "Default")
      (node (ref "U50") (pin "P5") (pinfunction "IO_L21P_T3_DQS_35_P5") (pintype "passive"))
    )
    (net (code "143") (name "/DDR3_DQ0") (class "Default")
      (node (ref "U50") (pin "Y1") (pinfunction "IO_L5N_T0_34_Y1") (pintype "passive"))
    )
    (net (code "144") (name "/DDR3_DQ1") (class "Default")
      (node (ref "U50") (pin "Y2") (pinfunction "IO_L4N_T0_34_Y2") (pintype "passive"))
    )
    (net (code "145") (name "/DDR3_DQ2") (class "Default")
      (node (ref "U50") (pin "W1") (pinfunction "IO_L5P_T0_34_W1") (pintype "passive"))
    )
    (net (code "146") (name "/DDR3_DQ3") (class "Default")
      (node (ref "U50") (pin "V2") (pinfunction "IO_L2N_T0_34_V2") (pintype "passive"))
    )
    (net (code "147") (name "/DDR3_DQ4") (class "Default")
      (node (ref "U50") (pin "U2") (pinfunction "IO_L2P_T0_34_U2") (pintype "passive"))
    )
    (net (code "148") (name "/DDR3_DQ5") (class "Default")
      (node (ref "U50") (pin "T1") (pinfunction "IO_L1P_T0_34_T1") (pintype "passive"))
    )
    (net (code "149") (name "/DDR3_DQ6") (class "Default")
      (node (ref "U50") (pin "U3") (pinfunction "IO_L6P_T0_34_U3") (pintype "passive"))
    )
    (net (code "150") (name "/DDR3_DQ7") (class "Default")
      (node (ref "U50") (pin "U1") (pinfunction "IO_L1N_T0_34_U1") (pintype "passive"))
    )
    (net (code "151") (name "/DDR3_DQ8") (class "Default")
      (node (ref "U50") (pin "W4") (pinfunction "IO_L12N_T1_MRCC_34_W4") (pintype "passive"))
    )
    (net (code "152") (name "/DDR3_DQ9") (class "Default")
      (node (ref "U50") (pin "AA4") (pinfunction "IO_L11N_T1_SRCC_34_AA4") (pintype "passive"))
    )
    (net (code "153") (name "/DDR3_DQ10") (class "Default")
      (node (ref "U50") (pin "Y4") (pinfunction "IO_L11P_T1_SRCC_34_Y4") (pintype "passive"))
    )
    (net (code "154") (name "/DDR3_DQ11") (class "Default")
      (node (ref "U50") (pin "AB3") (pinfunction "IO_L8P_T1_34_AB3") (pintype "passive"))
    )
    (net (code "155") (name "/DDR3_DQ12") (class "Default")
      (node (ref "U50") (pin "AB1") (pinfunction "IO_L7N_T1_34_AB1") (pintype "passive"))
    )
    (net (code "156") (name "/DDR3_DQ13") (class "Default")
      (node (ref "U50") (pin "AB5") (pinfunction "IO_L10N_T1_34_AB5") (pintype "passive"))
    )
    (net (code "157") (name "/DDR3_DQ14") (class "Default")
      (node (ref "U50") (pin "AA1") (pinfunction "IO_L7P_T1_34_AA1") (pintype "passive"))
    )
    (net (code "158") (name "/DDR3_DQ15") (class "Default")
      (node (ref "U50") (pin "AA5") (pinfunction "IO_L10P_T1_34_AA5") (pintype "passive"))
    )
    (net (code "159") (name "/DDR3_DQS0_N") (class "Default")
      (node (ref "U50") (pin "R2") (pinfunction "IO_L3N_T0_DQS_34_R2") (pintype "passive"))
    )
    (net (code "160") (name "/DDR3_DQS0_P") (class "Default")
      (node (ref "U50") (pin "R3") (pinfunction "IO_L3P_T0_DQS_34_R3") (pintype "passive"))
    )
    (net (code "161") (name "/DDR3_DQS1_N") (class "Default")
      (node (ref "U50") (pin "AA3") (pinfunction "IO_L9N_T1_DQS_34_AA3") (pintype "passive"))
    )
    (net (code "162") (name "/DDR3_DQS1_P") (class "Default")
      (node (ref "U50") (pin "Y3") (pinfunction "IO_L9P_T1_DQS_34_Y3") (pintype "passive"))
    )
    (net (code "163") (name "/DDR3_LDM0") (class "Default")
      (node (ref "U50") (pin "W2") (pinfunction "IO_L4P_T0_34_W2") (pintype "passive"))
    )
    (net (code "164") (name "/DDR3_ODT") (class "Default")
      (node (ref "U50") (pin "N4") (pinfunction "IO_L19P_T3_35_N4") (pintype "passive"))
    )
    (net (code "165") (name "/DDR3_RAS_N") (class "Default")
      (node (ref "U50") (pin "R1") (pinfunction "IO_L20P_T3_35_R1") (pintype "passive"))
    )
    (net (code "166") (name "/DDR3_RESET_N") (class "Default")
      (node (ref "U50") (pin "L4") (pinfunction "IO_L18N_T2_35_L4") (pintype "passive"))
    )
    (net (code "167") (name "/DDR3_UDM0") (class "Default")
      (node (ref "U50") (pin "AB2") (pinfunction "IO_L8N_T1_34_AB2") (pintype "passive"))
    )
    (net (code "168") (name "/DDR3_WE_N") (class "Default")
      (node (ref "U50") (pin "P1") (pinfunction "IO_L20N_T3_35_P1") (pintype "passive"))
    )
    (net (code "169") (name "/FLASH_RSTN") (class "Default")
      (node (ref "U50") (pin "W20") (pinfunction "IO_L12N_T1_MRCC_14_W20") (pintype "passive"))
    )
    (net (code "170") (name "/FLASH_WP_N") (class "Default")
      (node (ref "R95") (pin "1") (pinfunction "1_1") (pintype "passive"))
      (node (ref "U50") (pin "K17") (pinfunction "IO_L21P_T3_DQS_15_K17") (pintype "passive"))
    )
    (net (code "171") (name "/FPGA_CFG_A0") (class "Default")
      (node (ref "U50") (pin "R17") (pinfunction "IO_L24N_T3_A00_D16_14_R17") (pintype "passive"))
    )
    (net (code "172") (name "/FPGA_CFG_A1") (class "Default")
      (node (ref "U50") (pin "P16") (pinfunction "IO_L24P_T3_A01_D17_14_P16") (pintype "passive"))
    )
    (net (code "173") (name "/FPGA_CFG_A2") (class "Default")
      (node (ref "U50") (pin "N14") (pinfunction "IO_L23N_T3_A02_D18_14_N14") (pintype "passive"))
    )
    (net (code "174") (name "/FPGA_CFG_A3") (class "Default")
      (node (ref "U50") (pin "N13") (pinfunction "IO_L23P_T3_A03_D19_14_N13") (pintype "passive"))
    )
    (net (code "175") (name "/FPGA_CFG_A4") (class "Default")
      (node (ref "U50") (pin "R16") (pinfunction "IO_L22N_T3_A04_D20_14_R16") (pintype "passive"))
    )
    (net (code "176") (name "/FPGA_CFG_A5") (class "Default")
      (node (ref "U50") (pin "P15") (pinfunction "IO_L22P_T3_A05_D21_14_P15") (pintype "passive"))
    )
    (net (code "177") (name "/FPGA_CFG_A6") (class "Default")
      (node (ref "U50") (pin "P17") (pinfunction "IO_L21N_T3_DQS_A06_D22_14_P17") (pintype "passive"))
    )
    (net (code "178") (name "/FPGA_CFG_A7") (class "Default")
      (node (ref "U50") (pin "T18") (pinfunction "IO_L20N_T3_A07_D23_14_T18") (pintype "passive"))
    )
    (net (code "179") (name "/FPGA_CFG_A8") (class "Default")
      (node (ref "U50") (pin "R18") (pinfunction "IO_L20P_T3_A08_D24_14_R18") (pintype "passive"))
    )
    (net (code "180") (name "/FPGA_CFG_A9") (class "Default")
      (node (ref "U50") (pin "R14") (pinfunction "IO_L19N_T3_A09_D25_VREF_14_R14") (pintype "passive"))
    )
    (net (code "181") (name "/FPGA_CFG_A10") (class "Default")
      (node (ref "U50") (pin "P14") (pinfunction "IO_L19P_T3_A10_D26_14_P14") (pintype "passive"))
    )
    (net (code "182") (name "/FPGA_CFG_A11") (class "Default")
      (node (ref "U50") (pin "U18") (pinfunction "IO_L18N_T2_A11_D27_14_U18") (pintype "passive"))
    )
    (net (code "183") (name "/FPGA_CFG_A12") (class "Default")
      (node (ref "U50") (pin "U17") (pinfunction "IO_L18P_T2_A12_D28_14_U17") (pintype "passive"))
    )
    (net (code "184") (name "/FPGA_CFG_A13") (class "Default")
      (node (ref "U50") (pin "AB18") (pinfunction "IO_L17N_T2_A13_D29_14_AB18") (pintype "passive"))
    )
    (net (code "185") (name "/FPGA_CFG_A14") (class "Default")
      (node (ref "U50") (pin "AA18") (pinfunction "IO_L17P_T2_A14_D30_14_AA18") (pintype "passive"))
    )
    (net (code "186") (name "/FPGA_CFG_A15") (class "Default")
      (node (ref "U50") (pin "W17") (pinfunction "IO_L16N_T2_A15_D31_14_W17") (pintype "passive"))
    )
    (net (code "187") (name "/FPGA_CFG_A16") (class "Default")
      (node (ref "U50") (pin "L15") (pinfunction "IO_L22N_T3_A16_15_L15") (pintype "passive"))
    )
    (net (code "188") (name "/FPGA_CFG_A17") (class "Default")
      (node (ref "U50") (pin "L14") (pinfunction "IO_L22P_T3_A17_15_L14") (pintype "passive"))
    )
    (net (code "189") (name "/FPGA_CFG_A18") (class "Default")
      (node (ref "U50") (pin "J17") (pinfunction "IO_L21N_T3_DQS_A18_15_J17") (pintype "passive"))
    )
    (net (code "190") (name "/FPGA_CFG_A19") (class "Default")
      (node (ref "U50") (pin "L13") (pinfunction "IO_L20N_T3_A19_15_L13") (pintype "passive"))
    )
    (net (code "191") (name "/FPGA_CFG_A20") (class "Default")
      (node (ref "U50") (pin "M13") (pinfunction "IO_L20P_T3_A20_15_M13") (pintype "passive"))
    )
    (net (code "192") (name "/FPGA_CFG_A21") (class "Default")
      (node (ref "U50") (pin "K14") (pinfunction "IO_L19N_T3_A21_VREF_15_K14") (pintype "passive"))
    )
    (net (code "193") (name "/FPGA_CFG_A22") (class "Default")
      (node (ref "U50") (pin "K13") (pinfunction "IO_L19P_T3_A22_15_K13") (pintype "passive"))
    )
    (net (code "194") (name "/FPGA_CFG_A23") (class "Default")
      (node (ref "U50") (pin "M20") (pinfunction "IO_L18N_T2_A23_15_M20") (pintype "passive"))
    )
    (net (code "195") (name "/FPGA_CFG_A24") (class "Default")
      (node (ref "U50") (pin "N20") (pinfunction "IO_L18P_T2_A24_15_N20") (pintype "passive"))
    )
    (net (code "196") (name "/FPGA_CFG_A25") (class "Default")
      (node (ref "U50") (pin "N19") (pinfunction "IO_L17N_T2_A25_15_N19") (pintype "passive"))
    )
    (net (code "197") (name "/FPGA_CFG_CE_N") (class "Default")
      (node (ref "R40") (pin "1") (pinfunction "1_1") (pintype "passive"))
      (node (ref "U50") (pin "T19") (pinfunction "IO_L6P_T0_FCS_B_14_T19") (pintype "passive"))
    )
    (net (code "198") (name "/FPGA_CFG_D0") (class "Default")
      (node (ref "U50") (pin "P22") (pinfunction "IO_L1P_T0_D00_MOSI_14_P22") (pintype "passive"))
    )
    (net (code "199") (name "/FPGA_CFG_D1") (class "Default")
      (node (ref "U50") (pin "R22") (pinfunction "IO_L1N_T0_D01_DIN_14_R22") (pintype "passive"))
    )
    (net (code "200") (name "/FPGA_CFG_D2") (class "Default")
      (node (ref "U50") (pin "P21") (pinfunction "IO_L2P_T0_D02_14_P21") (pintype "passive"))
    )
    (net (code "201") (name "/FPGA_CFG_D3") (class "Default")
      (node (ref "U50") (pin "R21") (pinfunction "IO_L2N_T0_D03_14_R21") (pintype "passive"))
    )
    (net (code "202") (name "/FPGA_CFG_D4") (class "Default")
      (node (ref "U50") (pin "T21") (pinfunction "IO_L4P_T0_D04_14_T21") (pintype "passive"))
    )
    (net (code "203") (name "/FPGA_CFG_D5") (class "Default")
      (node (ref "U50") (pin "U21") (pinfunction "IO_L4N_T0_D05_14_U21") (pintype "passive"))
    )
    (net (code "204") (name "/FPGA_CFG_D6") (class "Default")
      (node (ref "U50") (pin "P19") (pinfunction "IO_L5P_T0_D06_14_P19") (pintype "passive"))
    )
    (net (code "205") (name "/FPGA_CFG_D7") (class "Default")
      (node (ref "U50") (pin "R19") (pinfunction "IO_L5N_T0_D07_14_R19") (pintype "passive"))
    )
    (net (code "206") (name "/FPGA_CFG_D8") (class "Default")
      (node (ref "U50") (pin "T20") (pinfunction "IO_L6N_T0_D08_VREF_14_T20") (pintype "passive"))
    )
    (net (code "207") (name "/FPGA_CFG_D9") (class "Default")
      (node (ref "U50") (pin "W21") (pinfunction "IO_L7P_T1_D09_14_W21") (pintype "passive"))
    )
    (net (code "208") (name "/FPGA_CFG_D10") (class "Default")
      (node (ref "U50") (pin "W22") (pinfunction "IO_L7N_T1_D10_14_W22") (pintype "passive"))
    )
    (net (code "209") (name "/FPGA_CFG_D11") (class "Default")
      (node (ref "U50") (pin "AA20") (pinfunction "IO_L8P_T1_D11_14_AA20") (pintype "passive"))
    )
    (net (code "210") (name "/FPGA_CFG_D12") (class "Default")
      (node (ref "U50") (pin "AA21") (pinfunction "IO_L8N_T1_D12_14_AA21") (pintype "passive"))
    )
    (net (code "211") (name "/FPGA_CFG_D13") (class "Default")
      (node (ref "U50") (pin "Y22") (pinfunction "IO_L9N_T1_DQS_D13_14_Y22") (pintype "passive"))
    )
    (net (code "212") (name "/FPGA_CFG_D14") (class "Default")
      (node (ref "U50") (pin "AB21") (pinfunction "IO_L10P_T1_D14_14_AB21") (pintype "passive"))
    )
    (net (code "213") (name "/FPGA_CFG_D15") (class "Default")
      (node (ref "U50") (pin "AB22") (pinfunction "IO_L10N_T1_D15_14_AB22") (pintype "passive"))
    )
    (net (code "214") (name "/FPGA_CFG_DONE") (class "Default")
      (node (ref "R94") (pin "1") (pinfunction "1_1") (pintype "passive"))
      (node (ref "U50") (pin "G11") (pinfunction "DONE_0_G11") (pintype "passive"))
    )
    (net (code "215") (name "/FPGA_CFG_INITB") (class "Default")
      (node (ref "R73") (pin "1") (pinfunction "1_1") (pintype "passive"))
      (node (ref "U50") (pin "U12") (pinfunction "INIT_B_0_U12") (pintype "passive"))
    )
    (net (code "216") (name "/FPGA_CFG_OE_N") (class "Default")
      (node (ref "R39") (pin "1") (pinfunction "1_1") (pintype "passive"))
      (node (ref "U50") (pin "L16") (pinfunction "IO_L23P_T3_FOE_B_15_L16") (pintype "passive"))
    )
    (net (code "217") (name "/FPGA_CFG_PROGRAM") (class "Default")
      (node (ref "R70") (pin "1") (pinfunction "1_1") (pintype "passive"))
      (node (ref "U50") (pin "N12") (pinfunction "PROGRAM_B_0_N12") (pintype "passive"))
      (node (ref "U69") (pin "2") (pinfunction "2_2") (pintype "passive"))
    )
    (net (code "218") (name "/FPGA_CFG_RS0") (class "Default")
      (node (ref "U50") (pin "M16") (pinfunction "IO_L24N_T3_RS0_15_M16") (pintype "passive"))
    )
    (net (code "219") (name "/FPGA_CFG_RS1") (class "Default")
      (node (ref "U50") (pin "M15") (pinfunction "IO_L24P_T3_RS1_15_M15") (pintype "passive"))
    )
    (net (code "220") (name "/FPGA_CFG_WE_N") (class "Default")
      (node (ref "R41") (pin "1") (pinfunction "1_1") (pintype "passive"))
      (node (ref "U50") (pin "K16") (pinfunction "IO_L23N_T3_FWE_B_15_K16") (pintype "passive"))
    )
    (net (code "221") (name "/JTAG_TCK") (class "Default")
      (node (ref "R223") (pin "1") (pinfunction "1_1") (pintype "passive"))
      (node (ref "U50") (pin "V12") (pinfunction "TCK_0_V12") (pintype "passive"))
    )
    (net (code "222") (name "/JTAG_TDI") (class "Default")
      (node (ref "R226") (pin "1") (pinfunction "1_1") (pintype "passive"))
      (node (ref "U50") (pin "R13") (pinfunction "TDI_0_R13") (pintype "passive"))
    )
    (net (code "223") (name "/JTAG_TDO") (class "Default")
      (node (ref "R225") (pin "1") (pinfunction "1_1") (pintype "passive"))
      (node (ref "U50") (pin "U13") (pinfunction "TDO_0_U13") (pintype "passive"))
    )
    (net (code "224") (name "/JTAG_TMS") (class "Default")
      (node (ref "R224") (pin "1") (pinfunction "1_1") (pintype "passive"))
      (node (ref "U50") (pin "T13") (pinfunction "TMS_0_T13") (pintype "passive"))
    )
    (net (code "225") (name "/MGT216_CLK0_N") (class "Default")
      (node (ref "U50") (pin "E6") (pinfunction "MGTREFCLK0N_216_E6") (pintype "passive"))
    )
    (net (code "226") (name "/MGT216_CLK0_P") (class "Default")
      (node (ref "U50") (pin "F6") (pinfunction "MGTREFCLK0P_216_F6") (pintype "passive"))
    )
    (net (code "227") (name "/MGT216_CLK1_N") (class "Default")
      (node (ref "U50") (pin "E10") (pinfunction "MGTREFCLK1N_216_E10") (pintype "passive"))
    )
    (net (code "228") (name "/MGT216_CLK1_P") (class "Default")
      (node (ref "U50") (pin "F10") (pinfunction "MGTREFCLK1P_216_F10") (pintype "passive"))
    )
    (net (code "229") (name "/MGT216_RX0_N") (class "Default")
      (node (ref "U50") (pin "A8") (pinfunction "MGTPRXN0_216_A8") (pintype "passive"))
    )
    (net (code "230") (name "/MGT216_RX0_P") (class "Default")
      (node (ref "U50") (pin "B8") (pinfunction "MGTPRXP0_216_B8") (pintype "passive"))
    )
    (net (code "231") (name "/MGT216_RX1_N") (class "Default")
      (node (ref "U50") (pin "C11") (pinfunction "MGTPRXN1_216_C11") (pintype "passive"))
    )
    (net (code "232") (name "/MGT216_RX1_P") (class "Default")
      (node (ref "U50") (pin "D11") (pinfunction "MGTPRXP1_216_D11") (pintype "passive"))
    )
    (net (code "233") (name "/MGT216_RX2_N") (class "Default")
      (node (ref "U50") (pin "A10") (pinfunction "MGTPRXN2_216_A10") (pintype "passive"))
    )
    (net (code "234") (name "/MGT216_RX2_P") (class "Default")
      (node (ref "U50") (pin "B10") (pinfunction "MGTPRXP2_216_B10") (pintype "passive"))
    )
    (net (code "235") (name "/MGT216_RX3_N") (class "Default")
      (node (ref "U50") (pin "C9") (pinfunction "MGTPRXN3_216_C9") (pintype "passive"))
    )
    (net (code "236") (name "/MGT216_RX3_P") (class "Default")
      (node (ref "U50") (pin "D9") (pinfunction "MGTPRXP3_216_D9") (pintype "passive"))
    )
    (net (code "237") (name "/MGT216_TX0_N") (class "Default")
      (node (ref "C489") (pin "1") (pinfunction "1_1") (pintype "passive"))
    )
    (net (code "238") (name "/MGT216_TX0_P") (class "Default")
      (node (ref "C490") (pin "1") (pinfunction "1_1") (pintype "passive"))
    )
    (net (code "239") (name "/MGT216_TX1_N") (class "Default")
      (node (ref "C491") (pin "1") (pinfunction "1_1") (pintype "passive"))
    )
    (net (code "240") (name "/MGT216_TX1_P") (class "Default")
      (node (ref "C492") (pin "1") (pinfunction "1_1") (pintype "passive"))
    )
    (net (code "241") (name "/MGT216_TX2_N") (class "Default")
      (node (ref "C497") (pin "1") (pinfunction "1_1") (pintype "passive"))
    )
    (net (code "242") (name "/MGT216_TX2_P") (class "Default")
      (node (ref "C496") (pin "1") (pinfunction "1_1") (pintype "passive"))
    )
    (net (code "243") (name "/MGT216_TX3_N") (class "Default")
      (node (ref "C495") (pin "1") (pinfunction "1_1") (pintype "passive"))
    )
    (net (code "244") (name "/MGT216_TX3_P") (class "Default")
      (node (ref "C494") (pin "1") (pinfunction "1_1") (pintype "passive"))
    )
    (net (code "245") (name "/SELECTMAP_CCLK") (class "Default")
      (node (ref "U50") (pin "L12") (pinfunction "CCLK_0_L12") (pintype "passive"))
    )
    (net (code "246") (name "/SELECTMAP_CSIB") (class "Default")
      (node (ref "U50") (pin "V17") (pinfunction "IO_L16P_T2_CSI_B_14_V17") (pintype "passive"))
    )
    (net (code "247") (name "/SELECTMAP_CSOB") (class "Default")
      (node (ref "U50") (pin "AB20") (pinfunction "IO_L15N_T2_DQS_DOUT_CSO_B_14_AB20") (pintype "passive"))
    )
    (net (code "248") (name "/SELECTMAP_RDWRB") (class "Default")
      (node (ref "U50") (pin "AA19") (pinfunction "IO_L15P_T2_DQS_RDWR_B_14_AA19") (pintype "passive"))
    )
    (net (code "249") (name "/SYS_200M_CLK_N") (class "Default")
      (node (ref "R87") (pin "1") (pinfunction "1_1") (pintype "passive"))
      (node (ref "R90") (pin "2") (pinfunction "2_2") (pintype "passive"))
      (node (ref "R91") (pin "1") (pinfunction "1_1") (pintype "passive"))
      (node (ref "U50") (pin "G4") (pinfunction "IO_L12N_T1_MRCC_35_G4") (pintype "passive"))
    )
    (net (code "250") (name "/SYS_200M_CLK_P") (class "Default")
      (node (ref "R87") (pin "2") (pinfunction "2_2") (pintype "passive"))
      (node (ref "R88") (pin "1") (pinfunction "1_1") (pintype "passive"))
      (node (ref "R89") (pin "2") (pinfunction "2_2") (pintype "passive"))
      (node (ref "U50") (pin "H4") (pinfunction "IO_L12P_T1_MRCC_35_H4") (pintype "passive"))
    )
    (net (code "251") (name "DDR_1V5") (class "Default")
      (node (ref "C483") (pin "2") (pinfunction "2_2") (pintype "passive"))
      (node (ref "R88") (pin "2") (pinfunction "2_2") (pintype "passive"))
      (node (ref "R91") (pin "2") (pinfunction "2_2") (pintype "passive"))
      (node (ref "U46") (pin "1") (pinfunction "VIN_1") (pintype "passive"))
      (node (ref "U46") (pin "3") (pinfunction "EN_3") (pintype "passive"))
    )
    (net (code "252") (name "DDR_3V3") (class "Default")
      (node (ref "R223") (pin "2") (pinfunction "2_2") (pintype "passive"))
      (node (ref "R224") (pin "2") (pinfunction "2_2") (pintype "passive"))
      (node (ref "R225") (pin "2") (pinfunction "2_2") (pintype "passive"))
      (node (ref "R226") (pin "2") (pinfunction "2_2") (pintype "passive"))
      (node (ref "R39") (pin "2") (pinfunction "2_2") (pintype "passive"))
      (node (ref "R40") (pin "2") (pinfunction "2_2") (pintype "passive"))
      (node (ref "R41") (pin "2") (pinfunction "2_2") (pintype "passive"))
      (node (ref "R70") (pin "2") (pinfunction "2_2") (pintype "passive"))
      (node (ref "R73") (pin "2") (pinfunction "2_2") (pintype "passive"))
      (node (ref "R94") (pin "2") (pinfunction "2_2") (pintype "passive"))
      (node (ref "R95") (pin "2") (pinfunction "2_2") (pintype "passive"))
      (node (ref "U50") (pin "U8") (pinfunction "CFGBVS_0_U8") (pintype "passive"))
    )
    (net (code "253") (name "GND") (class "Default")
      (node (ref "C134") (pin "1") (pinfunction "1_1") (pintype "passive"))
      (node (ref "C135") (pin "2") (pinfunction "2_2") (pintype "passive"))
      (node (ref "C227") (pin "1") (pinfunction "1_1") (pintype "passive"))
      (node (ref "C228") (pin "1") (pinfunction "1_1") (pintype "passive"))
      (node (ref "C320") (pin "1") (pinfunction "1_1") (pintype "passive"))
      (node (ref "C322") (pin "1") (pinfunction "1_1") (pintype "passive"))
      (node (ref "C326") (pin "1") (pinfunction "1_1") (pintype "passive"))
      (node (ref "C476") (pin "1") (pinfunction "1_1") (pintype "passive"))
      (node (ref "C477") (pin "1") (pinfunction "1_1") (pintype "passive"))
      (node (ref "C478") (pin "1") (pinfunction "1_1") (pintype "passive"))
      (node (ref "C479") (pin "1") (pinfunction "1_1") (pintype "passive"))
      (node (ref "C480") (pin "1") (pinfunction "1_1") (pintype "passive"))
      (node (ref "C481") (pin "1") (pinfunction "1_1") (pintype "passive"))
      (node (ref "C482") (pin "1") (pinfunction "1_1") (pintype "passive"))
      (node (ref "C483") (pin "1") (pinfunction "1_1") (pintype "passive"))
      (node (ref "C484") (pin "1") (pinfunction "1_1") (pintype "passive"))
      (node (ref "C485") (pin "1") (pinfunction "1_1") (pintype "passive"))
      (node (ref "C486") (pin "1") (pinfunction "1_1") (pintype "passive"))
      (node (ref "C487") (pin "1") (pinfunction "1_1") (pintype "passive"))
      (node (ref "C488") (pin "1") (pinfunction "1_1") (pintype "passive"))
      (node (ref "R89") (pin "1") (pinfunction "1_1") (pintype "passive"))
      (node (ref "R90") (pin "1") (pinfunction "1_1") (pintype "passive"))
      (node (ref "U46") (pin "2") (pinfunction "GND_2") (pintype "passive"))
      (node (ref "U50") (pin "E12") (pinfunction "VCCBATT_0_E12") (pintype "passive"))
      (node (ref "U50") (pin "K9") (pinfunction "GNDADC_0_K9") (pintype "passive"))
      (node (ref "U50") (pin "L10") (pinfunction "VP_0_L10") (pintype "passive"))
      (node (ref "U50") (pin "L9") (pinfunction "VREFN_0_L9") (pintype "passive"))
      (node (ref "U50") (pin "M10") (pinfunction "VREFP_0_M10") (pintype "passive"))
      (node (ref "U50") (pin "M9") (pinfunction "VN_0_M9") (pintype "passive"))
      (node (ref "U50") (pin "U22") (pinfunction "IO_L3P_T0_DQS_PUDC_B_14_U22") (pintype "passive"))
      (node (ref "U69") (pin "1") (pinfunction "1_1") (pintype "passive"))
    )
    (net (code "254") (name "MGTAVTT_1V2") (class "Default")
      (node (ref "C320") (pin "2") (pinfunction "2_2") (pintype "passive"))
      (node (ref "C322") (pin "2") (pinfunction "2_2") (pintype "passive"))
      (node (ref "C476") (pin "2") (pinfunction "2_2") (pintype "passive"))
      (node (ref "C477") (pin "2") (pinfunction "2_2") (pintype "passive"))
      (node (ref "C478") (pin "2") (pinfunction "2_2") (pintype "passive"))
      (node (ref "C482") (pin "2") (pinfunction "2_2") (pintype "passive"))
      (node (ref "C484") (pin "2") (pinfunction "2_2") (pintype "passive"))
      (node (ref "C485") (pin "2") (pinfunction "2_2") (pintype "passive"))
      (node (ref "C486") (pin "2") (pinfunction "2_2") (pintype "passive"))
      (node (ref "R96") (pin "2") (pinfunction "2_2") (pintype "passive"))
      (node (ref "U46") (pin "5") (pinfunction "VOUT_5") (pintype "passive"))
      (node (ref "U50") (pin "B11") (pinfunction "MGTAVTT_B11") (pintype "passive"))
      (node (ref "U50") (pin "B5") (pinfunction "MGTAVTT_B5") (pintype "passive"))
      (node (ref "U50") (pin "B7") (pinfunction "MGTAVTT_B7") (pintype "passive"))
      (node (ref "U50") (pin "B9") (pinfunction "MGTAVTT_B9") (pintype "passive"))
      (node (ref "U50") (pin "C4") (pinfunction "MGTAVTT_C4") (pintype "passive"))
      (node (ref "U50") (pin "C8") (pinfunction "MGTAVTT_C8") (pintype "passive"))
    )
    (net (code "255") (name "Net-(U50C-MGTPTXN0_216)") (class "Default")
      (node (ref "C489") (pin "2") (pinfunction "2_2") (pintype "passive"))
      (node (ref "U50") (pin "A4") (pinfunction "MGTPTXN0_216_A4") (pintype "passive"))
    )
    (net (code "256") (name "Net-(U50C-MGTPTXN1_216)") (class "Default")
      (node (ref "C491") (pin "2") (pinfunction "2_2") (pintype "passive"))
      (node (ref "U50") (pin "C5") (pinfunction "MGTPTXN1_216_C5") (pintype "passive"))
    )
    (net (code "257") (name "Net-(U50C-MGTPTXN2_216)") (class "Default")
      (node (ref "C497") (pin "2") (pinfunction "2_2") (pintype "passive"))
      (node (ref "U50") (pin "A6") (pinfunction "MGTPTXN2_216_A6") (pintype "passive"))
    )
    (net (code "258") (name "Net-(U50C-MGTPTXN3_216)") (class "Default")
      (node (ref "C495") (pin "2") (pinfunction "2_2") (pintype "passive"))
      (node (ref "U50") (pin "C7") (pinfunction "MGTPTXN3_216_C7") (pintype "passive"))
    )
    (net (code "259") (name "Net-(U50C-MGTPTXP0_216)") (class "Default")
      (node (ref "C490") (pin "2") (pinfunction "2_2") (pintype "passive"))
      (node (ref "U50") (pin "B4") (pinfunction "MGTPTXP0_216_B4") (pintype "passive"))
    )
    (net (code "260") (name "Net-(U50C-MGTPTXP1_216)") (class "Default")
      (node (ref "C492") (pin "2") (pinfunction "2_2") (pintype "passive"))
      (node (ref "U50") (pin "D5") (pinfunction "MGTPTXP1_216_D5") (pintype "passive"))
    )
    (net (code "261") (name "Net-(U50C-MGTPTXP2_216)") (class "Default")
      (node (ref "C496") (pin "2") (pinfunction "2_2") (pintype "passive"))
      (node (ref "U50") (pin "B6") (pinfunction "MGTPTXP2_216_B6") (pintype "passive"))
    )
    (net (code "262") (name "Net-(U50C-MGTPTXP3_216)") (class "Default")
      (node (ref "C494") (pin "2") (pinfunction "2_2") (pintype "passive"))
      (node (ref "U50") (pin "D7") (pinfunction "MGTPTXP3_216_D7") (pintype "passive"))
    )
    (net (code "263") (name "Net-(U50C-MGTRREF_216)") (class "Default")
      (node (ref "R96") (pin "1") (pinfunction "1_1") (pintype "passive"))
      (node (ref "U50") (pin "F8") (pinfunction "MGTRREF_216_F8") (pintype "passive"))
    )
    (net (code "264") (name "VCCAUX_1V8") (class "Default")
      (node (ref "U50") (pin "K10") (pinfunction "VCCADC_0_K10") (pintype "passive"))
    )
    (net (code "265") (name "VCCINT_1V0") (class "Default")
      (node (ref "C326") (pin "2") (pinfunction "2_2") (pintype "passive"))
      (node (ref "C479") (pin "2") (pinfunction "2_2") (pintype "passive"))
      (node (ref "C480") (pin "2") (pinfunction "2_2") (pintype "passive"))
      (node (ref "C481") (pin "2") (pinfunction "2_2") (pintype "passive"))
      (node (ref "C487") (pin "2") (pinfunction "2_2") (pintype "passive"))
      (node (ref "C488") (pin "2") (pinfunction "2_2") (pintype "passive"))
      (node (ref "U50") (pin "D10") (pinfunction "MGTAVCC_D10") (pintype "passive"))
      (node (ref "U50") (pin "D6") (pinfunction "MGTAVCC_D6") (pintype "passive"))
      (node (ref "U50") (pin "E8") (pinfunction "MGTAVCC_E8") (pintype "passive"))
      (node (ref "U50") (pin "F7") (pinfunction "MGTAVCC_F7") (pintype "passive"))
      (node (ref "U50") (pin "F9") (pinfunction "MGTAVCC_F9") (pintype "passive"))
    )
    (net (code "266") (name "VTTREF_0V75") (class "Default")
      (node (ref "C134") (pin "2") (pinfunction "2_2") (pintype "passive"))
      (node (ref "C135") (pin "1") (pinfunction "1_1") (pintype "passive"))
      (node (ref "C227") (pin "2") (pinfunction "2_2") (pintype "passive"))
      (node (ref "C228") (pin "2") (pinfunction "2_2") (pintype "passive"))
      (node (ref "U50") (pin "E3") (pinfunction "IO_L6N_T0_VREF_35_E3") (pintype "passive"))
      (node (ref "U50") (pin "N3") (pinfunction "IO_L19N_T3_VREF_35_N3") (pintype "passive"))
      (node (ref "U50") (pin "V3") (pinfunction "IO_L6N_T0_VREF_34_V3") (pintype "passive"))
      (node (ref "U50") (pin "W7") (pinfunction "IO_L19N_T3_VREF_34_W7") (pintype "passive"))
    )
    (net (code "267") (name "unconnected-(U46-BYP-Pad4)") (class "Default")
      (node (ref "U46") (pin "4") (pinfunction "BYP_4") (pintype "passive"))
    )
    (net (code "268") (name "unconnected-(U50A-DXN_0-PadN9)") (class "Default")
      (node (ref "U50") (pin "N9") (pinfunction "DXN_0_N9") (pintype "passive"))
    )
    (net (code "269") (name "unconnected-(U50A-DXP_0-PadN10)") (class "Default")
      (node (ref "U50") (pin "N10") (pinfunction "DXP_0_N10") (pintype "passive"))
    )
    (net (code "270") (name "unconnected-(U50A-IO_0_13-PadY17)") (class "Default")
      (node (ref "U50") (pin "Y17") (pinfunction "IO_0_13_Y17") (pintype "passive"))
    )
    (net (code "271") (name "unconnected-(U50A-IO_0_14-PadP20)") (class "Default")
      (node (ref "U50") (pin "P20") (pinfunction "IO_0_14_P20") (pintype "passive"))
    )
    (net (code "272") (name "unconnected-(U50A-IO_0_15-PadJ16)") (class "Default")
      (node (ref "U50") (pin "J16") (pinfunction "IO_0_15_J16") (pintype "passive"))
    )
    (net (code "273") (name "unconnected-(U50A-IO_25_14-PadN15)") (class "Default")
      (node (ref "U50") (pin "N15") (pinfunction "IO_25_14_N15") (pintype "passive"))
    )
    (net (code "274") (name "unconnected-(U50A-IO_L3N_T0_DQS_EMCCLK_14-PadV22)") (class "Default")
      (node (ref "U50") (pin "V22") (pinfunction "IO_L3N_T0_DQS_EMCCLK_14_V22") (pintype "passive"))
    )
    (net (code "275") (name "unconnected-(U50A-IO_L9P_T1_DQS_14-PadY21)") (class "Default")
      (node (ref "U50") (pin "Y21") (pinfunction "IO_L9P_T1_DQS_14_Y21") (pintype "passive"))
    )
    (net (code "276") (name "unconnected-(U50A-IO_L11N_T1_SRCC_14-PadV20)") (class "Default")
      (node (ref "U50") (pin "V20") (pinfunction "IO_L11N_T1_SRCC_14_V20") (pintype "passive"))
    )
    (net (code "277") (name "unconnected-(U50A-IO_L11P_T1_SRCC_14-PadU20)") (class "Default")
      (node (ref "U50") (pin "U20") (pinfunction "IO_L11P_T1_SRCC_14_U20") (pintype "passive"))
    )
    (net (code "278") (name "unconnected-(U50A-IO_L12P_T1_MRCC_14-PadW19)") (class "Default")
      (node (ref "U50") (pin "W19") (pinfunction "IO_L12P_T1_MRCC_14_W19") (pintype "passive"))
    )
    (net (code "279") (name "unconnected-(U50A-IO_L14N_T2_SRCC_14-PadV19)") (class "Default")
      (node (ref "U50") (pin "V19") (pinfunction "IO_L14N_T2_SRCC_14_V19") (pintype "passive"))
    )
    (net (code "280") (name "unconnected-(U50A-IO_L14P_T2_SRCC_14-PadV18)") (class "Default")
      (node (ref "U50") (pin "V18") (pinfunction "IO_L14P_T2_SRCC_14_V18") (pintype "passive"))
    )
    (net (code "281") (name "unconnected-(U50A-IO_L21P_T3_DQS_14-PadN17)") (class "Default")
      (node (ref "U50") (pin "N17") (pinfunction "IO_L21P_T3_DQS_14_N17") (pintype "passive"))
    )
    (net (code "282") (name "unconnected-(U50B-IO_0_16-PadF15)") (class "Default")
      (node (ref "U50") (pin "F15") (pinfunction "IO_0_16_F15") (pintype "passive"))
    )
    (net (code "283") (name "unconnected-(U50B-IO_0_34-PadT3)") (class "Default")
      (node (ref "U50") (pin "T3") (pinfunction "IO_0_34_T3") (pintype "passive"))
    )
    (net (code "284") (name "unconnected-(U50B-IO_25_15-PadM17)") (class "Default")
      (node (ref "U50") (pin "M17") (pinfunction "IO_25_15_M17") (pintype "passive"))
    )
    (net (code "285") (name "unconnected-(U50B-IO_25_16-PadF21)") (class "Default")
      (node (ref "U50") (pin "F21") (pinfunction "IO_25_16_F21") (pintype "passive"))
    )
    (net (code "286") (name "unconnected-(U50B-IO_L12P_T1_MRCC_34-PadV4)") (class "Default")
      (node (ref "U50") (pin "V4") (pinfunction "IO_L12P_T1_MRCC_34_V4") (pintype "passive"))
    )
    (net (code "287") (name "unconnected-(U50B-IO_L13N_T2_MRCC_34-PadT4)") (class "Default")
      (node (ref "U50") (pin "T4") (pinfunction "IO_L13N_T2_MRCC_34_T4") (pintype "passive"))
    )
    (net (code "288") (name "unconnected-(U50B-IO_L13P_T2_MRCC_34-PadR4)") (class "Default")
      (node (ref "U50") (pin "R4") (pinfunction "IO_L13P_T2_MRCC_34_R4") (pintype "passive"))
    )
    (net (code "289") (name "unconnected-(U50B-IO_L14N_T2_SRCC_34-PadU5)") (class "Default")
      (node (ref "U50") (pin "U5") (pinfunction "IO_L14N_T2_SRCC_34_U5") (pintype "passive"))
    )
    (net (code "290") (name "unconnected-(U50B-IO_L14P_T2_SRCC_34-PadT5)") (class "Default")
      (node (ref "U50") (pin "T5") (pinfunction "IO_L14P_T2_SRCC_34_T5") (pintype "passive"))
    )
    (net (code "291") (name "unconnected-(U50B-IO_L15N_T2_DQS_34-PadW5)") (class "Default")
      (node (ref "U50") (pin "W5") (pinfunction "IO_L15N_T2_DQS_34_W5") (pintype "passive"))
    )
    (net (code "292") (name "unconnected-(U50B-IO_L15P_T2_DQS_34-PadW6)") (class "Default")
      (node (ref "U50") (pin "W6") (pinfunction "IO_L15P_T2_DQS_34_W6") (pintype "passive"))
    )
    (net (code "293") (name "unconnected-(U50B-IO_L16N_T2_34-PadV5)") (class "Default")
      (node (ref "U50") (pin "V5") (pinfunction "IO_L16N_T2_34_V5") (pintype "passive"))
    )
    (net (code "294") (name "unconnected-(U50B-IO_L16P_T2_34-PadU6)") (class "Default")
      (node (ref "U50") (pin "U6") (pinfunction "IO_L16P_T2_34_U6") (pintype "passive"))
    )
    (net (code "295") (name "unconnected-(U50B-IO_L17P_T2_A26_15-PadN18)") (class "Default")
      (node (ref "U50") (pin "N18") (pinfunction "IO_L17P_T2_A26_15_N18") (pintype "passive"))
    )
    (net (code "296") (name "unconnected-(U50C-IO_0_35-PadF4)") (class "Default")
      (node (ref "U50") (pin "F4") (pinfunction "IO_0_35_F4") (pintype "passive"))
    )
    (net (code "297") (name "unconnected-(U50C-IO_25_34-PadU7)") (class "Default")
      (node (ref "U50") (pin "U7") (pinfunction "IO_25_34_U7") (pintype "passive"))
    )
    (net (code "298") (name "unconnected-(U50C-IO_25_35-PadL6)") (class "Default")
      (node (ref "U50") (pin "L6") (pinfunction "IO_25_35_L6") (pintype "passive"))
    )
    (net (code "299") (name "unconnected-(U50C-IO_L1N_T0_AD4N_35-PadA1)") (class "Default")
      (node (ref "U50") (pin "A1") (pinfunction "IO_L1N_T0_AD4N_35_A1") (pintype "passive"))
    )
    (net (code "300") (name "unconnected-(U50C-IO_L1P_T0_AD4P_35-PadB1)") (class "Default")
      (node (ref "U50") (pin "B1") (pinfunction "IO_L1P_T0_AD4P_35_B1") (pintype "passive"))
    )
    (net (code "301") (name "unconnected-(U50C-IO_L2N_T0_AD12N_35-PadB2)") (class "Default")
      (node (ref "U50") (pin "B2") (pinfunction "IO_L2N_T0_AD12N_35_B2") (pintype "passive"))
    )
    (net (code "302") (name "unconnected-(U50C-IO_L2P_T0_AD12P_35-PadC2)") (class "Default")
      (node (ref "U50") (pin "C2") (pinfunction "IO_L2P_T0_AD12P_35_C2") (pintype "passive"))
    )
    (net (code "303") (name "unconnected-(U50C-IO_L3N_T0_DQS_AD5N_35-PadD1)") (class "Default")
      (node (ref "U50") (pin "D1") (pinfunction "IO_L3N_T0_DQS_AD5N_35_D1") (pintype "passive"))
    )
    (net (code "304") (name "unconnected-(U50C-IO_L3P_T0_DQS_AD5P_35-PadE1)") (class "Default")
      (node (ref "U50") (pin "E1") (pinfunction "IO_L3P_T0_DQS_AD5P_35_E1") (pintype "passive"))
    )
    (net (code "305") (name "unconnected-(U50C-IO_L4N_T0_35-PadD2)") (class "Default")
      (node (ref "U50") (pin "D2") (pinfunction "IO_L4N_T0_35_D2") (pintype "passive"))
    )
    (net (code "306") (name "unconnected-(U50C-IO_L4P_T0_35-PadE2)") (class "Default")
      (node (ref "U50") (pin "E2") (pinfunction "IO_L4P_T0_35_E2") (pintype "passive"))
    )
    (net (code "307") (name "unconnected-(U50C-IO_L5N_T0_AD13N_35-PadF1)") (class "Default")
      (node (ref "U50") (pin "F1") (pinfunction "IO_L5N_T0_AD13N_35_F1") (pintype "passive"))
    )
    (net (code "308") (name "unconnected-(U50C-IO_L5P_T0_AD13P_35-PadG1)") (class "Default")
      (node (ref "U50") (pin "G1") (pinfunction "IO_L5P_T0_AD13P_35_G1") (pintype "passive"))
    )
    (net (code "309") (name "unconnected-(U50C-IO_L6P_T0_35-PadF3)") (class "Default")
      (node (ref "U50") (pin "F3") (pinfunction "IO_L6P_T0_35_F3") (pintype "passive"))
    )
    (net (code "310") (name "unconnected-(U50C-IO_L10N_T1_AD15N_35-PadH5)") (class "Default")
      (node (ref "U50") (pin "H5") (pinfunction "IO_L10N_T1_AD15N_35_H5") (pintype "passive"))
    )
    (net (code "311") (name "unconnected-(U50C-IO_L13N_T2_MRCC_35-PadJ4)") (class "Default")
      (node (ref "U50") (pin "J4") (pinfunction "IO_L13N_T2_MRCC_35_J4") (pintype "passive"))
    )
    (net (code "312") (name "unconnected-(U50C-IO_L17N_T2_34-PadT6)") (class "Default")
      (node (ref "U50") (pin "T6") (pinfunction "IO_L17N_T2_34_T6") (pintype "passive"))
    )
    (net (code "313") (name "unconnected-(U50C-IO_L17N_T2_35-PadJ6)") (class "Default")
      (node (ref "U50") (pin "J6") (pinfunction "IO_L17N_T2_35_J6") (pintype "passive"))
    )
    (net (code "314") (name "unconnected-(U50C-IO_L17P_T2_34-PadR6)") (class "Default")
      (node (ref "U50") (pin "R6") (pinfunction "IO_L17P_T2_34_R6") (pintype "passive"))
    )
    (net (code "315") (name "unconnected-(U50C-IO_L17P_T2_35-PadK6)") (class "Default")
      (node (ref "U50") (pin "K6") (pinfunction "IO_L17P_T2_35_K6") (pintype "passive"))
    )
    (net (code "316") (name "unconnected-(U50C-IO_L18N_T2_34-PadAA6)") (class "Default")
      (node (ref "U50") (pin "AA6") (pinfunction "IO_L18N_T2_34_AA6") (pintype "passive"))
    )
    (net (code "317") (name "unconnected-(U50C-IO_L18P_T2_34-PadY6)") (class "Default")
      (node (ref "U50") (pin "Y6") (pinfunction "IO_L18P_T2_34_Y6") (pintype "passive"))
    )
    (net (code "318") (name "unconnected-(U50C-IO_L19P_T3_34-PadV7)") (class "Default")
      (node (ref "U50") (pin "V7") (pinfunction "IO_L19P_T3_34_V7") (pintype "passive"))
    )
    (net (code "319") (name "unconnected-(U50C-IO_L20N_T3_34-PadAB6)") (class "Default")
      (node (ref "U50") (pin "AB6") (pinfunction "IO_L20N_T3_34_AB6") (pintype "passive"))
    )
    (net (code "320") (name "unconnected-(U50C-IO_L20P_T3_34-PadAB7)") (class "Default")
      (node (ref "U50") (pin "AB7") (pinfunction "IO_L20P_T3_34_AB7") (pintype "passive"))
    )
    (net (code "321") (name "unconnected-(U50C-IO_L21N_T3_DQS_34-PadV8)") (class "Default")
      (node (ref "U50") (pin "V8") (pinfunction "IO_L21N_T3_DQS_34_V8") (pintype "passive"))
    )
    (net (code "322") (name "unconnected-(U50C-IO_L21P_T3_DQS_34-PadV9)") (class "Default")
      (node (ref "U50") (pin "V9") (pinfunction "IO_L21P_T3_DQS_34_V9") (pintype "passive"))
    )
    (net (code "323") (name "unconnected-(U50C-IO_L22N_T3_34-PadAB8)") (class "Default")
      (node (ref "U50") (pin "AB8") (pinfunction "IO_L22N_T3_34_AB8") (pintype "passive"))
    )
    (net (code "324") (name "unconnected-(U50C-IO_L22P_T3_34-PadAA8)") (class "Default")
      (node (ref "U50") (pin "AA8") (pinfunction "IO_L22P_T3_34_AA8") (pintype "passive"))
    )
    (net (code "325") (name "unconnected-(U50C-IO_L23N_T3_34-PadY7)") (class "Default")
      (node (ref "U50") (pin "Y7") (pinfunction "IO_L23N_T3_34_Y7") (pintype "passive"))
    )
    (net (code "326") (name "unconnected-(U50C-IO_L23P_T3_34-PadY8)") (class "Default")
      (node (ref "U50") (pin "Y8") (pinfunction "IO_L23P_T3_34_Y8") (pintype "passive"))
    )
    (net (code "327") (name "unconnected-(U50C-IO_L23P_T3_35-PadM6)") (class "Default")
      (node (ref "U50") (pin "M6") (pinfunction "IO_L23P_T3_35_M6") (pintype "passive"))
    )
    (net (code "328") (name "unconnected-(U50C-IO_L24N_T3_34-PadY9)") (class "Default")
      (node (ref "U50") (pin "Y9") (pinfunction "IO_L24N_T3_34_Y9") (pintype "passive"))
    )
    (net (code "329") (name "unconnected-(U50C-IO_L24P_T3_34-PadW9)") (class "Default")
      (node (ref "U50") (pin "W9") (pinfunction "IO_L24P_T3_34_W9") (pintype "passive"))
    )
    (net (code "330") (name "unconnected-(U50C-IO_L24P_T3_35-PadP6)") (class "Default")
      (node (ref "U50") (pin "P6") (pinfunction "IO_L24P_T3_35_P6") (pintype "passive"))
    )
  )
)
